# imu_v2.net
KiCad netlist of a schematic drawn in EAGLE
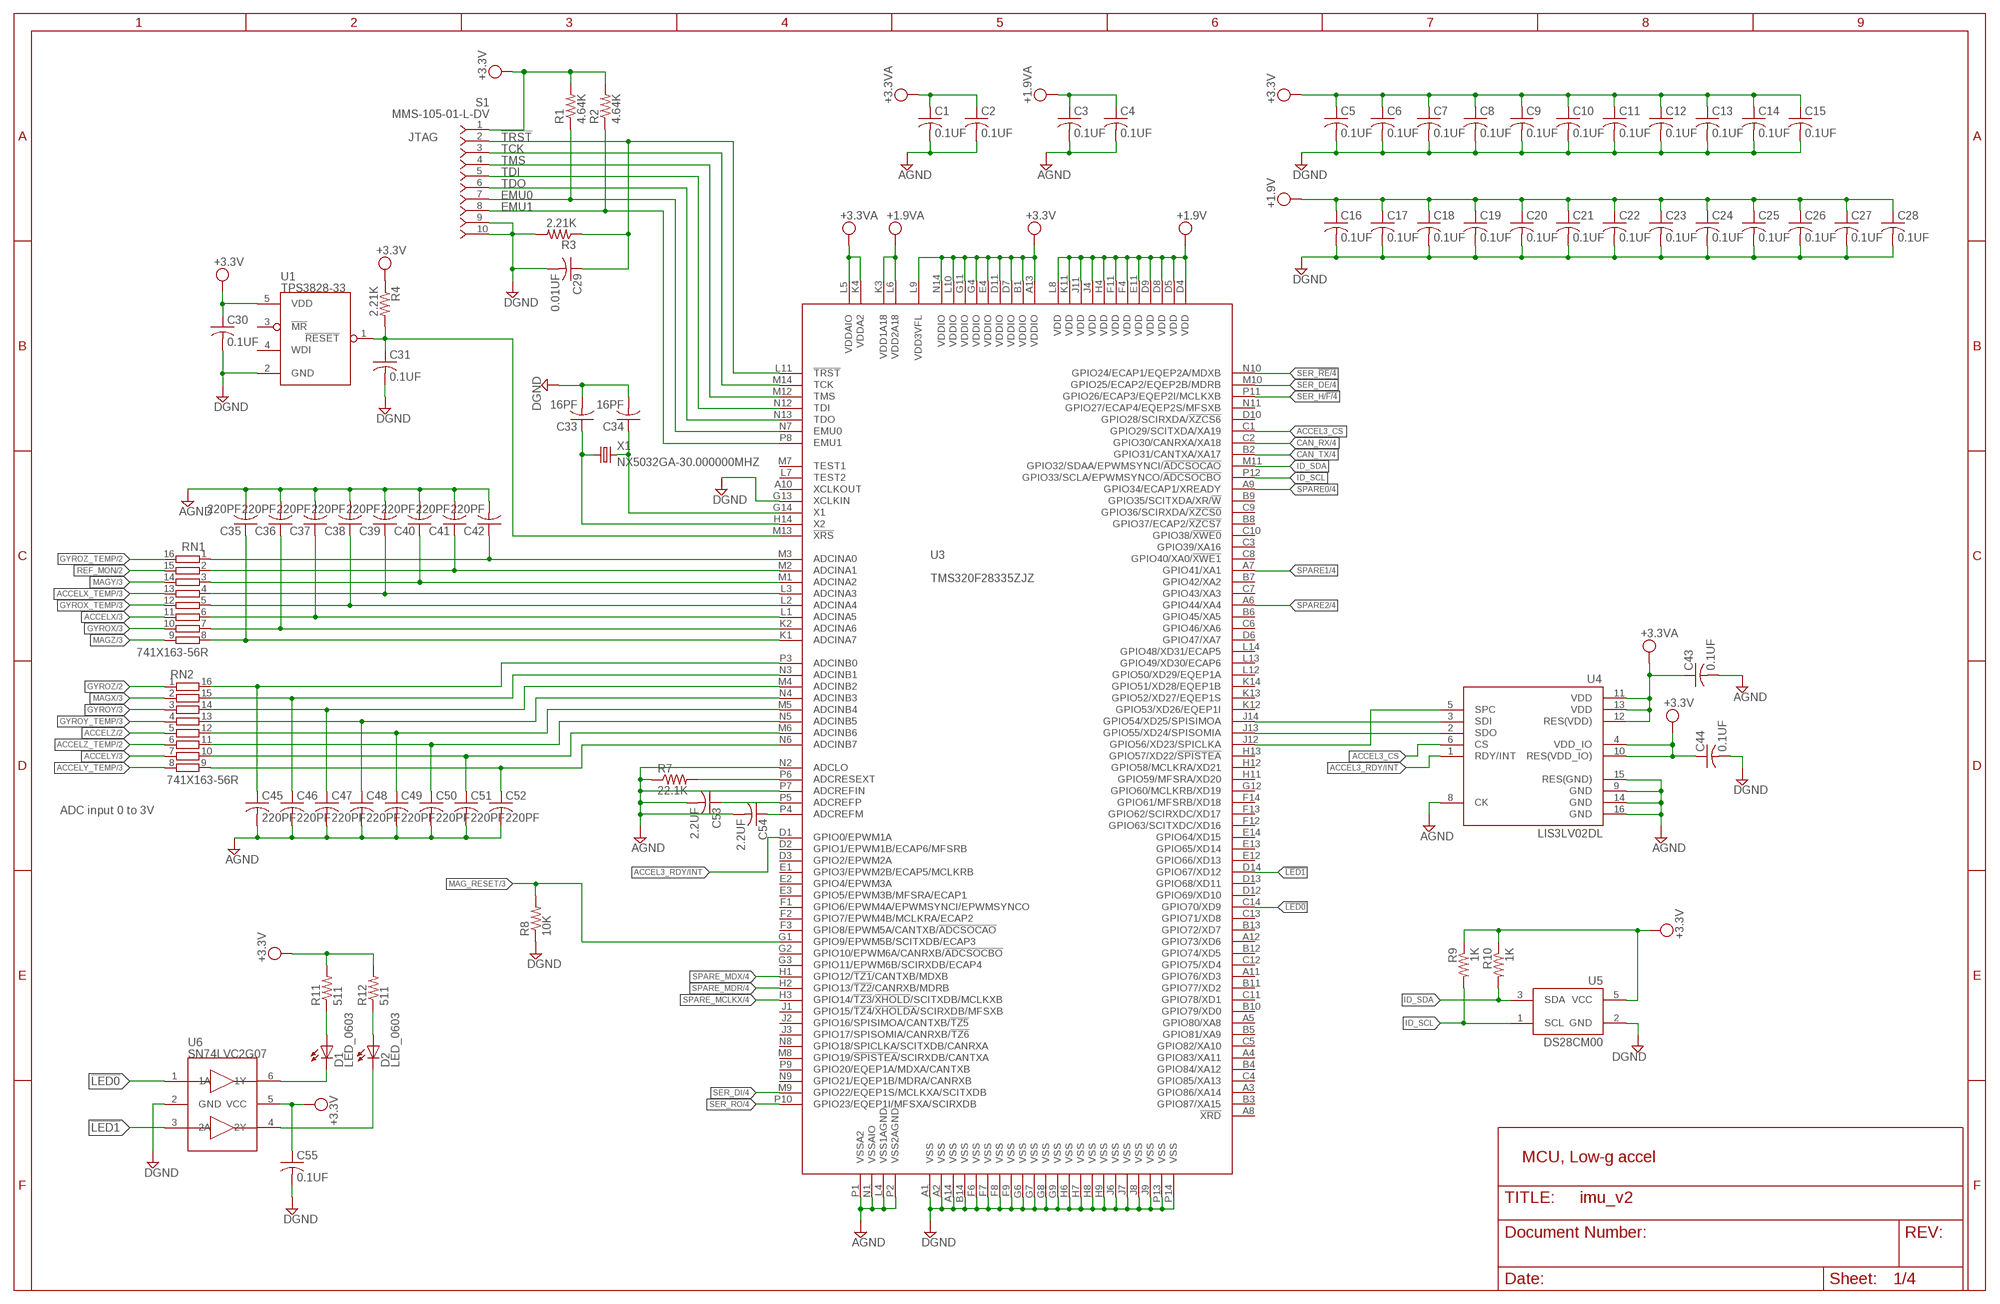
[diagram p0: schematic, sheet 1]
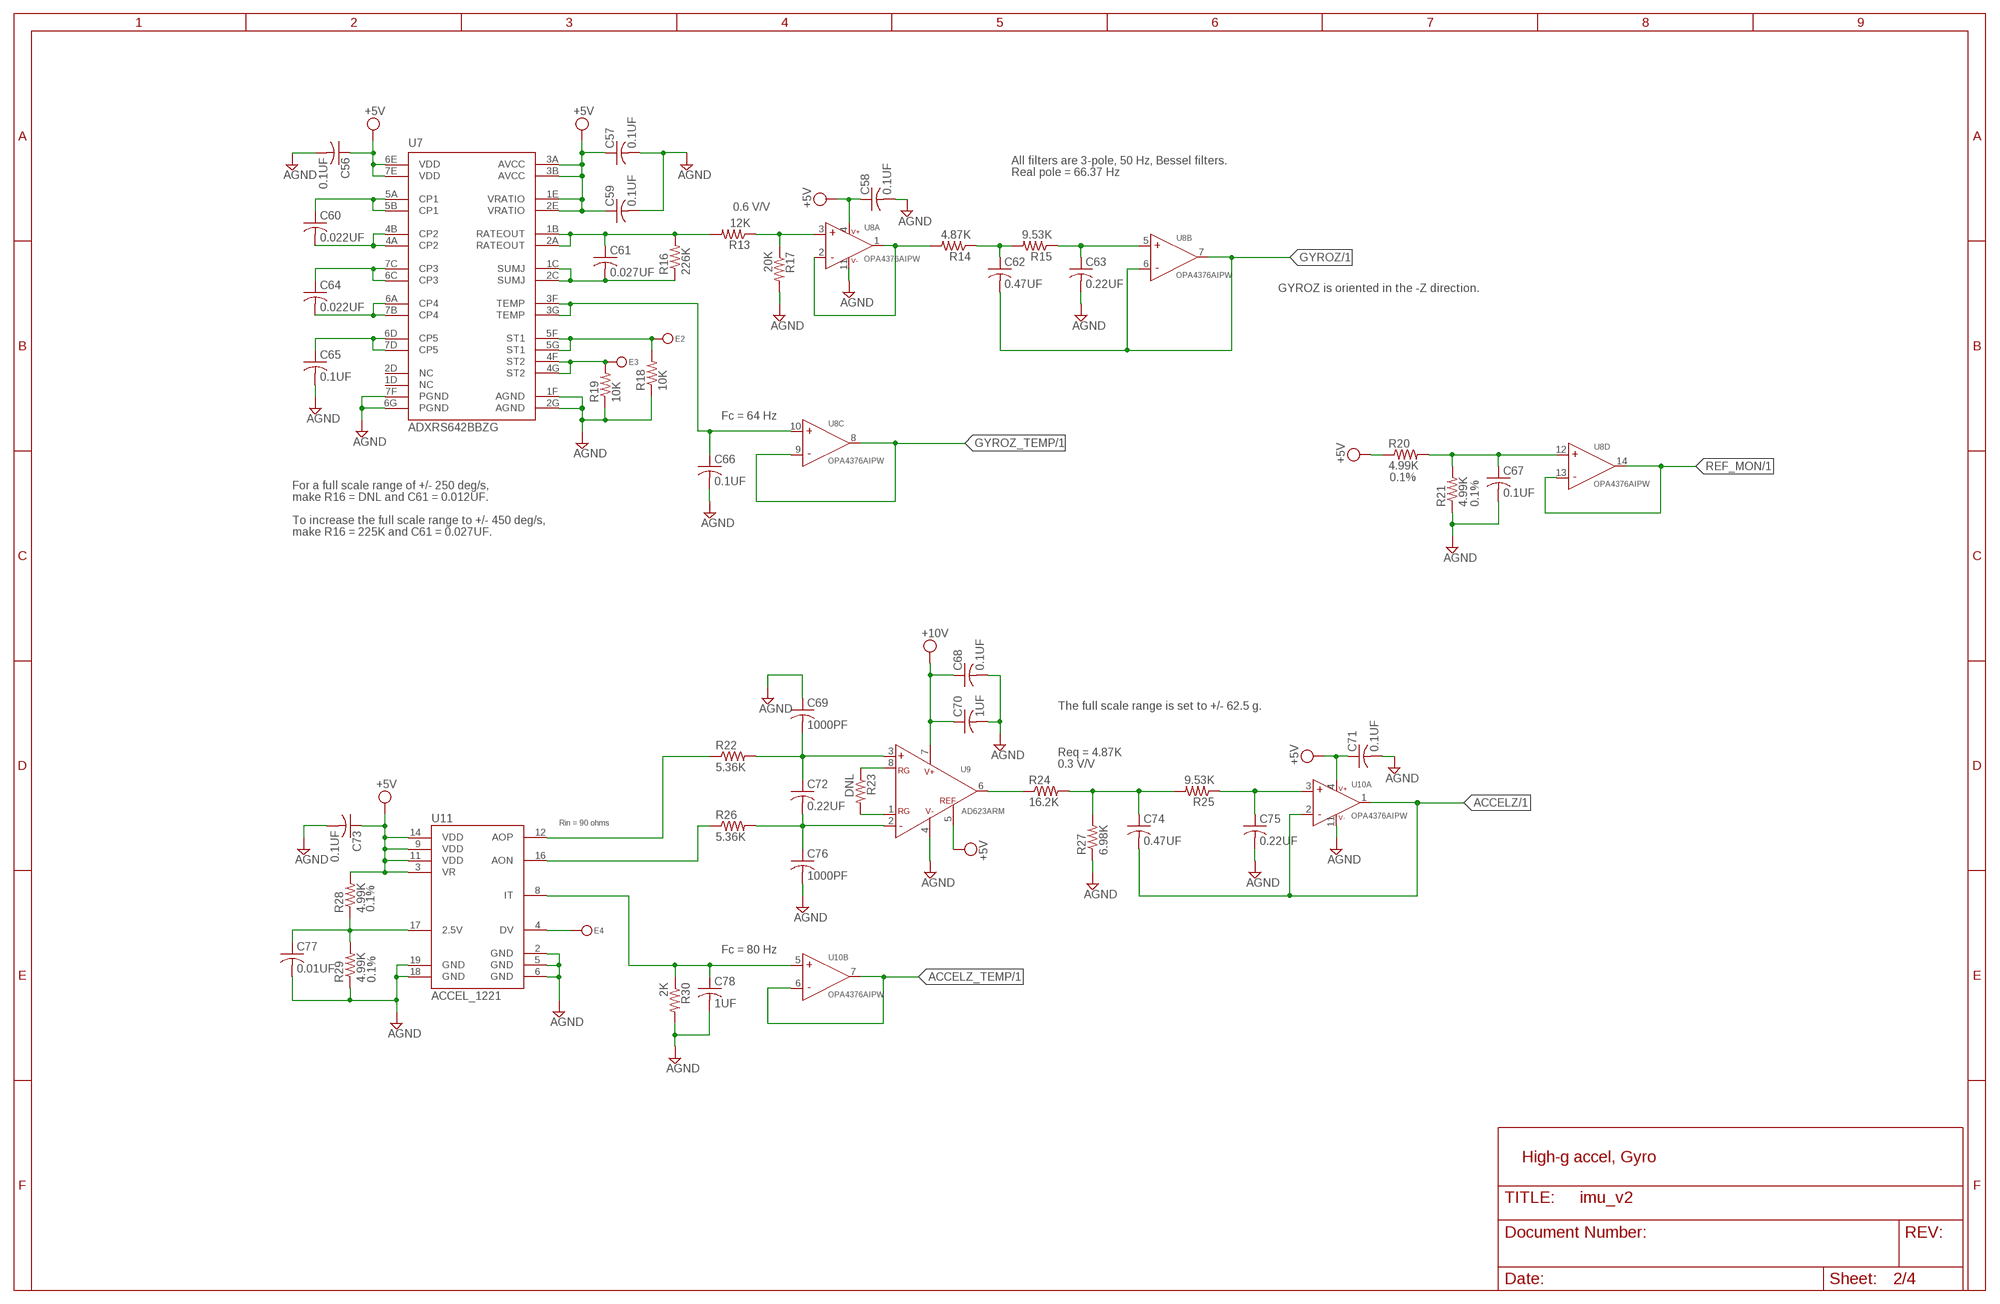
[diagram p1: schematic, sheet 2]
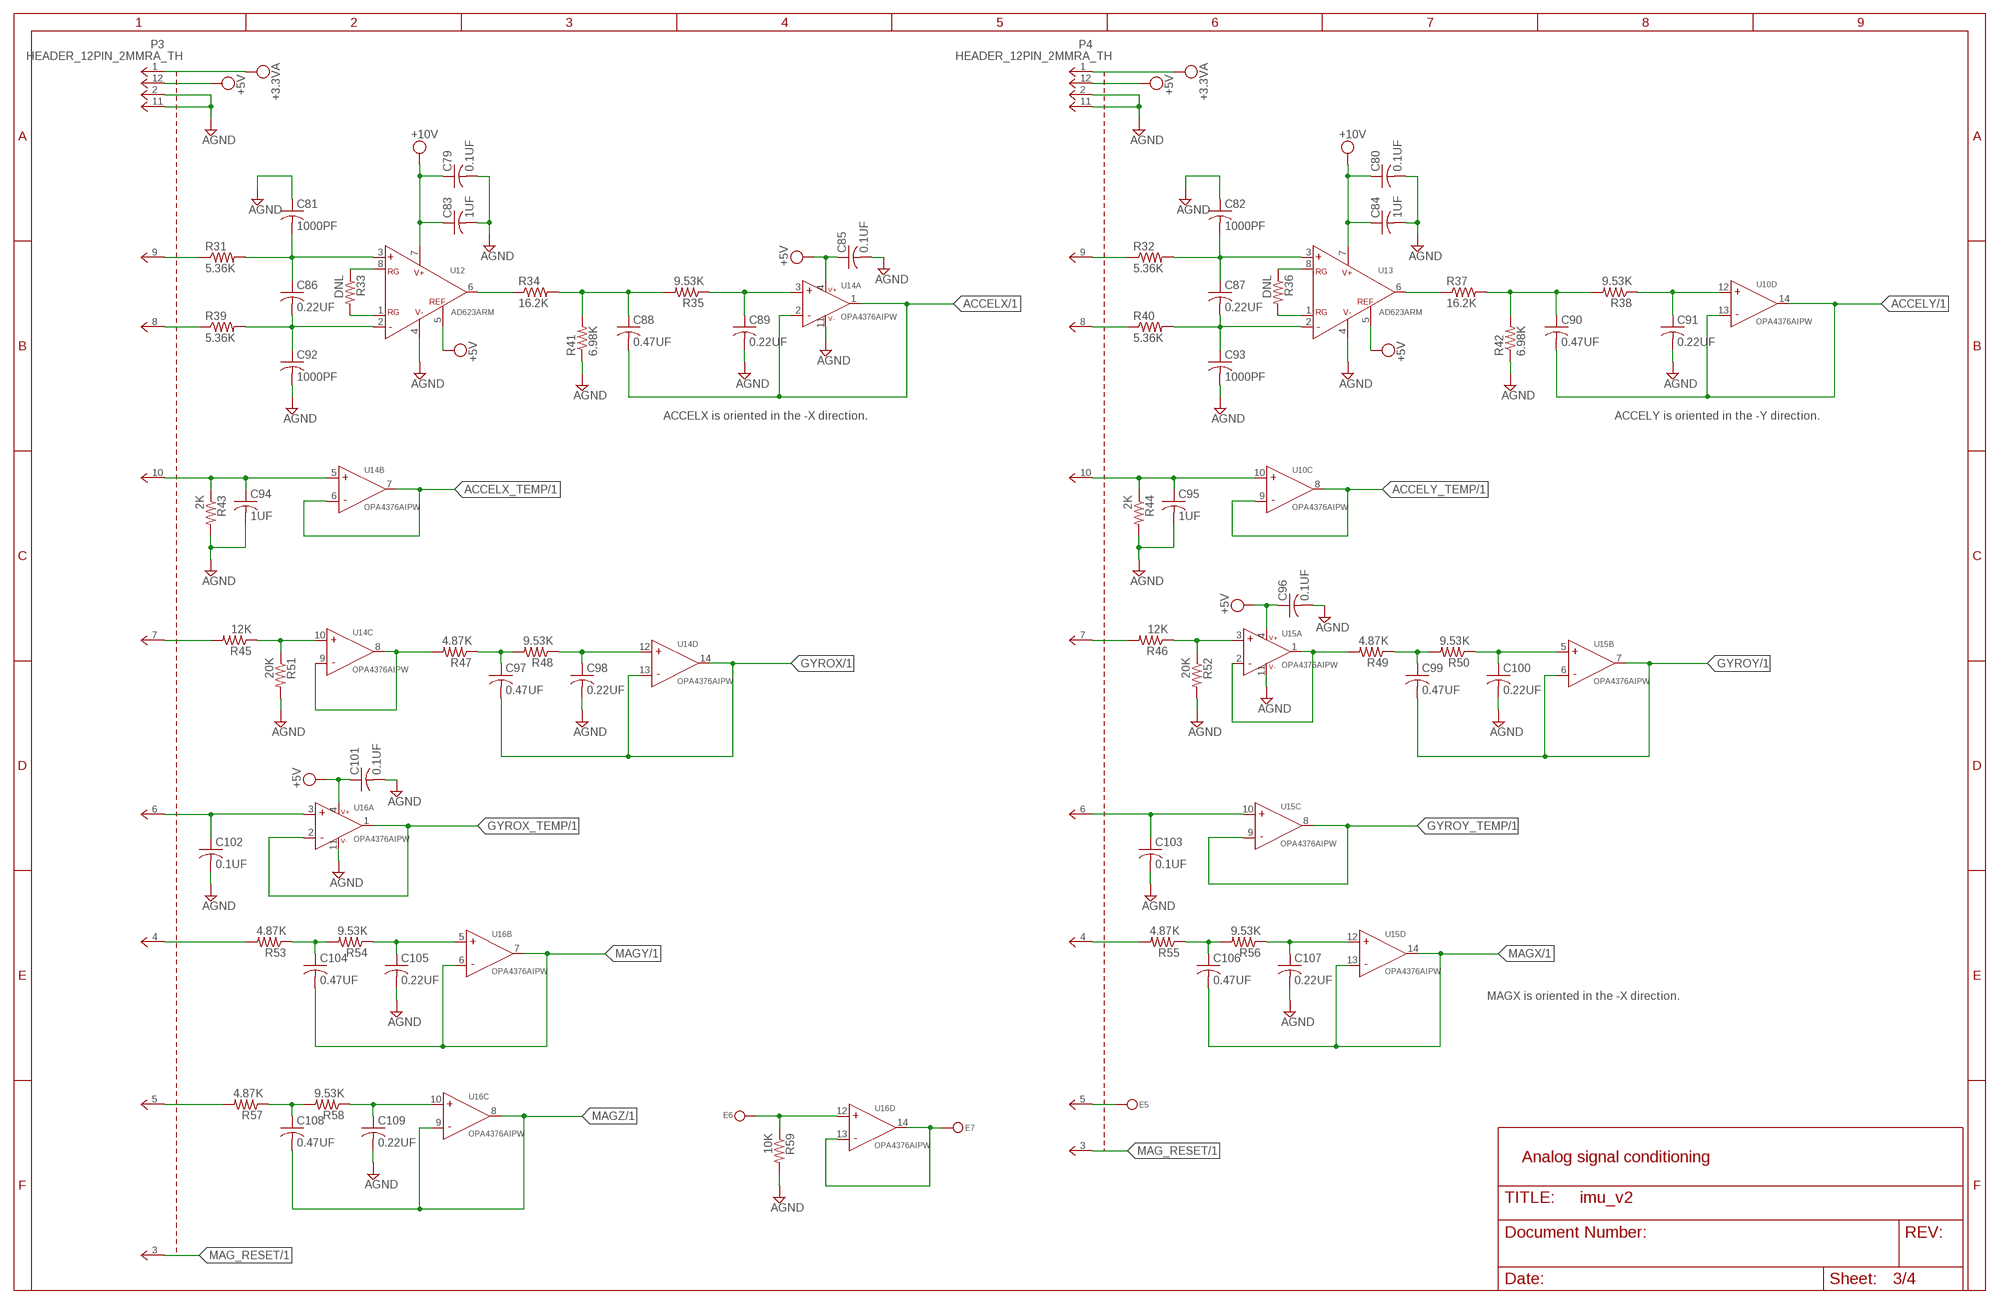
[diagram p2: schematic, sheet 3]
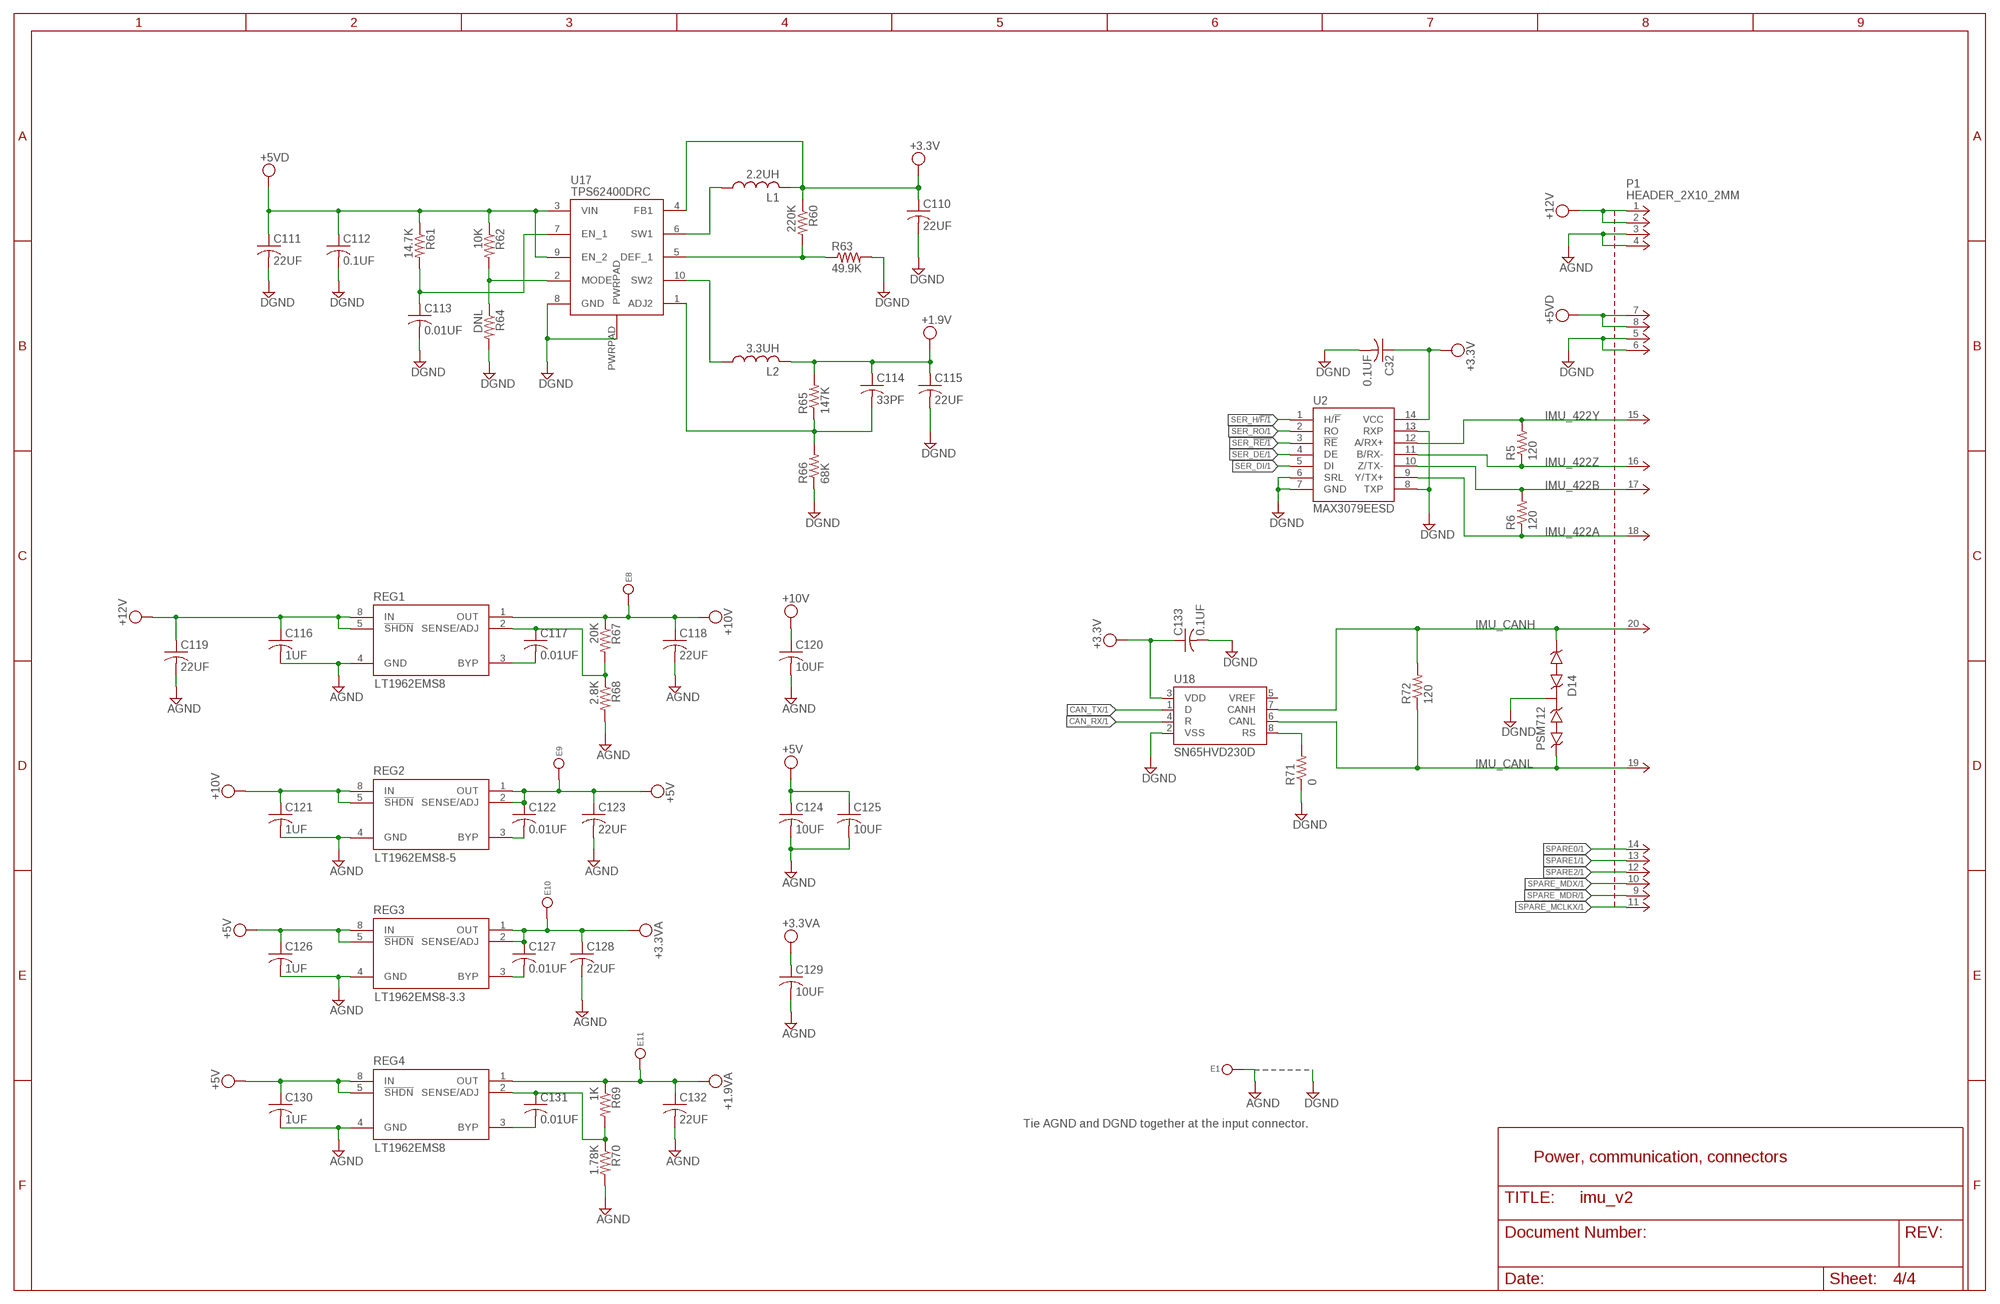
[diagram p3: schematic, sheet 4]

(export (version "E")
  (design (tool "Eeschema 10.0.6"))
  (components
    (comp (ref "C32")
      (value "0.1UF")
      (footprint "eagle-import:C0603K")
      (libsource (lib "eagle-import") (part "C-USC0603K"))
    )
    (comp (ref "C110")
      (value "22UF")
      (footprint "eagle-import:C1210K")
      (libsource (lib "eagle-import") (part "C-USC1210K"))
    )
    (comp (ref "C111")
      (value "22UF")
      (footprint "eagle-import:C1210K")
      (libsource (lib "eagle-import") (part "C-USC1210K"))
    )
    (comp (ref "C112")
      (value "0.1UF")
      (footprint "eagle-import:C0603K")
      (libsource (lib "eagle-import") (part "C-USC0603K"))
    )
    (comp (ref "C113")
      (value "0.01UF")
      (footprint "eagle-import:C0603K")
      (libsource (lib "eagle-import") (part "C-USC0603K"))
    )
    (comp (ref "C114")
      (value "33PF")
      (footprint "eagle-import:C0603K")
      (libsource (lib "eagle-import") (part "C-USC0603K"))
    )
    (comp (ref "C115")
      (value "22UF")
      (footprint "eagle-import:C1210K")
      (libsource (lib "eagle-import") (part "C-USC1210K"))
    )
    (comp (ref "C116")
      (value "1UF")
      (footprint "eagle-import:C0603K")
      (libsource (lib "eagle-import") (part "C-USC0603K"))
    )
    (comp (ref "C117")
      (value "0.01UF")
      (footprint "eagle-import:C0603K")
      (libsource (lib "eagle-import") (part "C-USC0603K"))
    )
    (comp (ref "C118")
      (value "22UF")
      (footprint "eagle-import:C1210K")
      (libsource (lib "eagle-import") (part "C-USC1210K"))
    )
    (comp (ref "C119")
      (value "22UF")
      (footprint "eagle-import:C1210K")
      (libsource (lib "eagle-import") (part "C-USC1210K"))
    )
    (comp (ref "C120")
      (value "10UF")
      (footprint "eagle-import:C1206K")
      (libsource (lib "eagle-import") (part "C-USC1206K"))
    )
    (comp (ref "C121")
      (value "1UF")
      (footprint "eagle-import:C0603K")
      (libsource (lib "eagle-import") (part "C-USC0603K"))
    )
    (comp (ref "C122")
      (value "0.01UF")
      (footprint "eagle-import:C0603K")
      (libsource (lib "eagle-import") (part "C-USC0603K"))
    )
    (comp (ref "C123")
      (value "22UF")
      (footprint "eagle-import:C1210K")
      (libsource (lib "eagle-import") (part "C-USC1210K"))
    )
    (comp (ref "C124")
      (value "10UF")
      (footprint "eagle-import:C1206K")
      (libsource (lib "eagle-import") (part "C-USC1206K"))
    )
    (comp (ref "C125")
      (value "10UF")
      (footprint "eagle-import:C1206K")
      (libsource (lib "eagle-import") (part "C-USC1206K"))
    )
    (comp (ref "C126")
      (value "1UF")
      (footprint "eagle-import:C0603K")
      (libsource (lib "eagle-import") (part "C-USC0603K"))
    )
    (comp (ref "C127")
      (value "0.01UF")
      (footprint "eagle-import:C0603K")
      (libsource (lib "eagle-import") (part "C-USC0603K"))
    )
    (comp (ref "C128")
      (value "22UF")
      (footprint "eagle-import:C1210K")
      (libsource (lib "eagle-import") (part "C-USC1210K"))
    )
    (comp (ref "C129")
      (value "10UF")
      (footprint "eagle-import:C1206K")
      (libsource (lib "eagle-import") (part "C-USC1206K"))
    )
    (comp (ref "C130")
      (value "1UF")
      (footprint "eagle-import:C0603K")
      (libsource (lib "eagle-import") (part "C-USC0603K"))
    )
    (comp (ref "C131")
      (value "0.01UF")
      (footprint "eagle-import:C0603K")
      (libsource (lib "eagle-import") (part "C-USC0603K"))
    )
    (comp (ref "C132")
      (value "22UF")
      (footprint "eagle-import:C1210K")
      (libsource (lib "eagle-import") (part "C-USC1210K"))
    )
    (comp (ref "C133")
      (value "0.1UF")
      (footprint "eagle-import:C0603K")
      (libsource (lib "eagle-import") (part "C-USC0603K"))
    )
    (comp (ref "D14")
      (value "PSM712")
      (footprint "eagle-import:SOT23")
      (libsource (lib "eagle-import") (part "PSM712"))
    )
    (comp (ref "E1")
      (value "5015_TESTCLIP")
      (footprint "eagle-import:5015_TESTCLIP")
      (libsource (lib "eagle-import") (part "5015_TESTCLIP"))
    )
    (comp (ref "E8")
      (value "TP30")
      (footprint "eagle-import:TP30")
      (libsource (lib "eagle-import") (part "TP30"))
    )
    (comp (ref "E9")
      (value "TP30")
      (footprint "eagle-import:TP30")
      (libsource (lib "eagle-import") (part "TP30"))
    )
    (comp (ref "E10")
      (value "TP30")
      (footprint "eagle-import:TP30")
      (libsource (lib "eagle-import") (part "TP30"))
    )
    (comp (ref "E11")
      (value "TP30")
      (footprint "eagle-import:TP30")
      (libsource (lib "eagle-import") (part "TP30"))
    )
    (comp (ref "L1")
      (value "2.2UH")
      (footprint "eagle-import:VLF3010A")
      (libsource (lib "eagle-import") (part "LVLF3010A2.2_UH"))
    )
    (comp (ref "L2")
      (value "3.3UH")
      (footprint "eagle-import:VLF3010A")
      (libsource (lib "eagle-import") (part "LVLF3010A3.3_UH"))
    )
    (comp (ref "P1")
      (value "HEADER_2X10_2MM")
      (footprint "eagle-import:HEADER_2X10_2MM")
      (libsource (lib "eagle-import") (part "HEADER_2X10_2MM"))
    )
    (comp (ref "R5")
      (value "120")
      (footprint "eagle-import:R0603")
      (libsource (lib "eagle-import") (part "R-US_R0603"))
    )
    (comp (ref "R6")
      (value "120")
      (footprint "eagle-import:R0603")
      (libsource (lib "eagle-import") (part "R-US_R0603"))
    )
    (comp (ref "R60")
      (value "220K")
      (footprint "eagle-import:R0603")
      (libsource (lib "eagle-import") (part "R-US_R0603"))
    )
    (comp (ref "R61")
      (value "14.7K")
      (footprint "eagle-import:R0603")
      (libsource (lib "eagle-import") (part "R-US_R0603"))
    )
    (comp (ref "R62")
      (value "10K")
      (footprint "eagle-import:R0603")
      (libsource (lib "eagle-import") (part "R-US_R0603"))
    )
    (comp (ref "R63")
      (value "49.9K")
      (footprint "eagle-import:R0603")
      (libsource (lib "eagle-import") (part "R-US_R0603"))
    )
    (comp (ref "R64")
      (value "DNL")
      (footprint "eagle-import:R0603")
      (libsource (lib "eagle-import") (part "R-US_R0603"))
    )
    (comp (ref "R65")
      (value "147K")
      (footprint "eagle-import:R0603")
      (libsource (lib "eagle-import") (part "R-US_R0603"))
    )
    (comp (ref "R66")
      (value "68K")
      (footprint "eagle-import:R0603")
      (libsource (lib "eagle-import") (part "R-US_R0603"))
    )
    (comp (ref "R67")
      (value "20K")
      (footprint "eagle-import:R0603")
      (libsource (lib "eagle-import") (part "R-US_R0603"))
    )
    (comp (ref "R68")
      (value "2.8K")
      (footprint "eagle-import:R0603")
      (libsource (lib "eagle-import") (part "R-US_R0603"))
    )
    (comp (ref "R69")
      (value "1K")
      (footprint "eagle-import:R0603")
      (libsource (lib "eagle-import") (part "R-US_R0603"))
    )
    (comp (ref "R70")
      (value "1.78K")
      (footprint "eagle-import:R0603")
      (libsource (lib "eagle-import") (part "R-US_R0603"))
    )
    (comp (ref "R71")
      (value "0")
      (footprint "eagle-import:R0603")
      (libsource (lib "eagle-import") (part "R-US_R0603"))
    )
    (comp (ref "R72")
      (value "120")
      (footprint "eagle-import:R0603")
      (libsource (lib "eagle-import") (part "R-US_R0603"))
    )
    (comp (ref "REG1")
      (value "LT1962EMS8")
      (footprint "eagle-import:MSOP8")
      (libsource (lib "eagle-import") (part "LT162EMS89"))
    )
    (comp (ref "REG2")
      (value "LT1962EMS8-5")
      (footprint "eagle-import:MSOP8")
      (libsource (lib "eagle-import") (part "LT162EMS8-59"))
    )
    (comp (ref "REG3")
      (value "LT1962EMS8-3.3")
      (footprint "eagle-import:MSOP8")
      (libsource (lib "eagle-import") (part "LT162EMS8-3.39"))
    )
    (comp (ref "REG4")
      (value "LT1962EMS8")
      (footprint "eagle-import:MSOP8")
      (libsource (lib "eagle-import") (part "LT162EMS89"))
    )
    (comp (ref "U2")
      (value "MAX3079EESD")
      (footprint "eagle-import:SOIC14-NARROW")
      (libsource (lib "eagle-import") (part "MAX3079EESD"))
    )
    (comp (ref "U17")
      (value "TPS62400DRC")
      (footprint "eagle-import:QFN10")
      (libsource (lib "eagle-import") (part "TPS624DRC00"))
    )
    (comp (ref "U18")
      (value "SN65HVD230D")
      (footprint "eagle-import:SO08")
      (libsource (lib "eagle-import") (part "SN65HVD230D"))
    )
    (comp (ref "C56")
      (value "0.1UF")
      (footprint "eagle-import:C0603K")
      (libsource (lib "eagle-import") (part "C-USC0603K"))
    )
    (comp (ref "C57")
      (value "0.1UF")
      (footprint "eagle-import:C0603K")
      (libsource (lib "eagle-import") (part "C-USC0603K"))
    )
    (comp (ref "C58")
      (value "0.1UF")
      (footprint "eagle-import:C0603K")
      (libsource (lib "eagle-import") (part "C-USC0603K"))
    )
    (comp (ref "C59")
      (value "0.1UF")
      (footprint "eagle-import:C0603K")
      (libsource (lib "eagle-import") (part "C-USC0603K"))
    )
    (comp (ref "C60")
      (value "0.022UF")
      (footprint "eagle-import:C0603K")
      (libsource (lib "eagle-import") (part "C-USC0603K"))
    )
    (comp (ref "C61")
      (value "0.027UF")
      (footprint "eagle-import:C0603K")
      (libsource (lib "eagle-import") (part "C-USC0603K"))
    )
    (comp (ref "C62")
      (value "0.47UF")
      (footprint "eagle-import:C0603K")
      (libsource (lib "eagle-import") (part "C-USC0603K"))
    )
    (comp (ref "C63")
      (value "0.22UF")
      (footprint "eagle-import:C0603K")
      (libsource (lib "eagle-import") (part "C-USC0603K"))
    )
    (comp (ref "C64")
      (value "0.022UF")
      (footprint "eagle-import:C0603K")
      (libsource (lib "eagle-import") (part "C-USC0603K"))
    )
    (comp (ref "C65")
      (value "0.1UF")
      (footprint "eagle-import:C0603K")
      (libsource (lib "eagle-import") (part "C-USC0603K"))
    )
    (comp (ref "C66")
      (value "0.1UF")
      (footprint "eagle-import:C0603K")
      (libsource (lib "eagle-import") (part "C-USC0603K"))
    )
    (comp (ref "C67")
      (value "0.1UF")
      (footprint "eagle-import:C0603K")
      (libsource (lib "eagle-import") (part "C-USC0603K"))
    )
    (comp (ref "C68")
      (value "0.1UF")
      (footprint "eagle-import:C0603K")
      (libsource (lib "eagle-import") (part "C-USC0603K"))
    )
    (comp (ref "C69")
      (value "1000PF")
      (footprint "eagle-import:C0603K")
      (libsource (lib "eagle-import") (part "C-USC0603K"))
    )
    (comp (ref "C70")
      (value "1UF")
      (footprint "eagle-import:C0603K")
      (libsource (lib "eagle-import") (part "C-USC0603K"))
    )
    (comp (ref "C71")
      (value "0.1UF")
      (footprint "eagle-import:C0603K")
      (libsource (lib "eagle-import") (part "C-USC0603K"))
    )
    (comp (ref "C72")
      (value "0.22UF")
      (footprint "eagle-import:C0603K")
      (libsource (lib "eagle-import") (part "C-USC0603K"))
    )
    (comp (ref "C73")
      (value "0.1UF")
      (footprint "eagle-import:C0603K")
      (libsource (lib "eagle-import") (part "C-USC0603K"))
    )
    (comp (ref "C74")
      (value "0.47UF")
      (footprint "eagle-import:C0603K")
      (libsource (lib "eagle-import") (part "C-USC0603K"))
    )
    (comp (ref "C75")
      (value "0.22UF")
      (footprint "eagle-import:C0603K")
      (libsource (lib "eagle-import") (part "C-USC0603K"))
    )
    (comp (ref "C76")
      (value "1000PF")
      (footprint "eagle-import:C0603K")
      (libsource (lib "eagle-import") (part "C-USC0603K"))
    )
    (comp (ref "C77")
      (value "0.01UF")
      (footprint "eagle-import:C0603K")
      (libsource (lib "eagle-import") (part "C-USC0603K"))
    )
    (comp (ref "C78")
      (value "1UF")
      (footprint "eagle-import:C0603K")
      (libsource (lib "eagle-import") (part "C-USC0603K"))
    )
    (comp (ref "E2")
      (value "TP30")
      (footprint "eagle-import:TP30")
      (libsource (lib "eagle-import") (part "TP30"))
    )
    (comp (ref "E3")
      (value "TP30")
      (footprint "eagle-import:TP30")
      (libsource (lib "eagle-import") (part "TP30"))
    )
    (comp (ref "E4")
      (value "TP30")
      (footprint "eagle-import:TP30")
      (libsource (lib "eagle-import") (part "TP30"))
    )
    (comp (ref "R13")
      (value "12K")
      (footprint "eagle-import:R0603")
      (libsource (lib "eagle-import") (part "R-US_R0603"))
    )
    (comp (ref "R14")
      (value "4.87K")
      (footprint "eagle-import:R0603")
      (libsource (lib "eagle-import") (part "R-US_R0603"))
    )
    (comp (ref "R15")
      (value "9.53K")
      (footprint "eagle-import:R0603")
      (libsource (lib "eagle-import") (part "R-US_R0603"))
    )
    (comp (ref "R16")
      (value "226K")
      (footprint "eagle-import:R0603")
      (libsource (lib "eagle-import") (part "R-US_R0603"))
    )
    (comp (ref "R17")
      (value "20K")
      (footprint "eagle-import:R0603")
      (libsource (lib "eagle-import") (part "R-US_R0603"))
    )
    (comp (ref "R18")
      (value "10K")
      (footprint "eagle-import:R0603")
      (libsource (lib "eagle-import") (part "R-US_R0603"))
    )
    (comp (ref "R19")
      (value "10K")
      (footprint "eagle-import:R0603")
      (libsource (lib "eagle-import") (part "R-US_R0603"))
    )
    (comp (ref "R20")
      (value "4.99K")
      (footprint "eagle-import:R0603")
      (fields (field (name "TOL") "0.1%"))
      (libsource (lib "eagle-import") (part "R-US_R0603"))
    )
    (comp (ref "R21")
      (value "4.99K")
      (footprint "eagle-import:R0603")
      (fields (field (name "TOL") "0.1%"))
      (libsource (lib "eagle-import") (part "R-US_R0603"))
    )
    (comp (ref "R22")
      (value "5.36K")
      (footprint "eagle-import:R0603")
      (libsource (lib "eagle-import") (part "R-US_R0603"))
    )
    (comp (ref "R23")
      (value "DNL")
      (footprint "eagle-import:R0603")
      (libsource (lib "eagle-import") (part "R-US_R0603"))
    )
    (comp (ref "R24")
      (value "16.2K")
      (footprint "eagle-import:R0603")
      (libsource (lib "eagle-import") (part "R-US_R0603"))
    )
    (comp (ref "R25")
      (value "9.53K")
      (footprint "eagle-import:R0603")
      (libsource (lib "eagle-import") (part "R-US_R0603"))
    )
    (comp (ref "R26")
      (value "5.36K")
      (footprint "eagle-import:R0603")
      (libsource (lib "eagle-import") (part "R-US_R0603"))
    )
    (comp (ref "R27")
      (value "6.98K")
      (footprint "eagle-import:R0603")
      (libsource (lib "eagle-import") (part "R-US_R0603"))
    )
    (comp (ref "R28")
      (value "4.99K")
      (footprint "eagle-import:R0603")
      (fields (field (name "TOL") "0.1%"))
      (libsource (lib "eagle-import") (part "R-US_R0603"))
    )
    (comp (ref "R29")
      (value "4.99K")
      (footprint "eagle-import:R0603")
      (fields (field (name "TOL") "0.1%"))
      (libsource (lib "eagle-import") (part "R-US_R0603"))
    )
    (comp (ref "R30")
      (value "2K")
      (footprint "eagle-import:R0603")
      (libsource (lib "eagle-import") (part "R-US_R0603"))
    )
    (comp (ref "U7")
      (value "ADXRS642BBZG")
      (footprint "eagle-import:ADXRS_CBGA32")
      (libsource (lib "eagle-import") (part "ADXRSBBZG642"))
    )
    (comp (ref "U8")
      (value "OPA4376AIPW")
      (footprint "eagle-import:TSSOP14")
      (libsource (lib "eagle-import") (part "OPA4376AIPW"))
    )
    (comp (ref "U9")
      (value "AD623ARM")
      (footprint "eagle-import:MSOP8")
      (libsource (lib "eagle-import") (part "AD623ARM"))
    )
    (comp (ref "U10")
      (value "OPA4376AIPW")
      (footprint "eagle-import:TSSOP14")
      (libsource (lib "eagle-import") (part "OPA4376AIPW"))
    )
    (comp (ref "U11")
      (value "ACCEL_1221")
      (footprint "eagle-import:1221_LCC")
      (libsource (lib "eagle-import") (part "ACCEL_1221"))
    )
    (comp (ref "C79")
      (value "0.1UF")
      (footprint "eagle-import:C0603K")
      (libsource (lib "eagle-import") (part "C-USC0603K"))
    )
    (comp (ref "C80")
      (value "0.1UF")
      (footprint "eagle-import:C0603K")
      (libsource (lib "eagle-import") (part "C-USC0603K"))
    )
    (comp (ref "C81")
      (value "1000PF")
      (footprint "eagle-import:C0603K")
      (libsource (lib "eagle-import") (part "C-USC0603K"))
    )
    (comp (ref "C82")
      (value "1000PF")
      (footprint "eagle-import:C0603K")
      (libsource (lib "eagle-import") (part "C-USC0603K"))
    )
    (comp (ref "C83")
      (value "1UF")
      (footprint "eagle-import:C0603K")
      (libsource (lib "eagle-import") (part "C-USC0603K"))
    )
    (comp (ref "C84")
      (value "1UF")
      (footprint "eagle-import:C0603K")
      (libsource (lib "eagle-import") (part "C-USC0603K"))
    )
    (comp (ref "C85")
      (value "0.1UF")
      (footprint "eagle-import:C0603K")
      (libsource (lib "eagle-import") (part "C-USC0603K"))
    )
    (comp (ref "C86")
      (value "0.22UF")
      (footprint "eagle-import:C0603K")
      (libsource (lib "eagle-import") (part "C-USC0603K"))
    )
    (comp (ref "C87")
      (value "0.22UF")
      (footprint "eagle-import:C0603K")
      (libsource (lib "eagle-import") (part "C-USC0603K"))
    )
    (comp (ref "C88")
      (value "0.47UF")
      (footprint "eagle-import:C0603K")
      (libsource (lib "eagle-import") (part "C-USC0603K"))
    )
    (comp (ref "C89")
      (value "0.22UF")
      (footprint "eagle-import:C0603K")
      (libsource (lib "eagle-import") (part "C-USC0603K"))
    )
    (comp (ref "C90")
      (value "0.47UF")
      (footprint "eagle-import:C0603K")
      (libsource (lib "eagle-import") (part "C-USC0603K"))
    )
    (comp (ref "C91")
      (value "0.22UF")
      (footprint "eagle-import:C0603K")
      (libsource (lib "eagle-import") (part "C-USC0603K"))
    )
    (comp (ref "C92")
      (value "1000PF")
      (footprint "eagle-import:C0603K")
      (libsource (lib "eagle-import") (part "C-USC0603K"))
    )
    (comp (ref "C93")
      (value "1000PF")
      (footprint "eagle-import:C0603K")
      (libsource (lib "eagle-import") (part "C-USC0603K"))
    )
    (comp (ref "C94")
      (value "1UF")
      (footprint "eagle-import:C0603K")
      (libsource (lib "eagle-import") (part "C-USC0603K"))
    )
    (comp (ref "C95")
      (value "1UF")
      (footprint "eagle-import:C0603K")
      (libsource (lib "eagle-import") (part "C-USC0603K"))
    )
    (comp (ref "C96")
      (value "0.1UF")
      (footprint "eagle-import:C0603K")
      (libsource (lib "eagle-import") (part "C-USC0603K"))
    )
    (comp (ref "C97")
      (value "0.47UF")
      (footprint "eagle-import:C0603K")
      (libsource (lib "eagle-import") (part "C-USC0603K"))
    )
    (comp (ref "C98")
      (value "0.22UF")
      (footprint "eagle-import:C0603K")
      (libsource (lib "eagle-import") (part "C-USC0603K"))
    )
    (comp (ref "C99")
      (value "0.47UF")
      (footprint "eagle-import:C0603K")
      (libsource (lib "eagle-import") (part "C-USC0603K"))
    )
    (comp (ref "C100")
      (value "0.22UF")
      (footprint "eagle-import:C0603K")
      (libsource (lib "eagle-import") (part "C-USC0603K"))
    )
    (comp (ref "C101")
      (value "0.1UF")
      (footprint "eagle-import:C0603K")
      (libsource (lib "eagle-import") (part "C-USC0603K"))
    )
    (comp (ref "C102")
      (value "0.1UF")
      (footprint "eagle-import:C0603K")
      (libsource (lib "eagle-import") (part "C-USC0603K"))
    )
    (comp (ref "C103")
      (value "0.1UF")
      (footprint "eagle-import:C0603K")
      (libsource (lib "eagle-import") (part "C-USC0603K"))
    )
    (comp (ref "C104")
      (value "0.47UF")
      (footprint "eagle-import:C0603K")
      (libsource (lib "eagle-import") (part "C-USC0603K"))
    )
    (comp (ref "C105")
      (value "0.22UF")
      (footprint "eagle-import:C0603K")
      (libsource (lib "eagle-import") (part "C-USC0603K"))
    )
    (comp (ref "C106")
      (value "0.47UF")
      (footprint "eagle-import:C0603K")
      (libsource (lib "eagle-import") (part "C-USC0603K"))
    )
    (comp (ref "C107")
      (value "0.22UF")
      (footprint "eagle-import:C0603K")
      (libsource (lib "eagle-import") (part "C-USC0603K"))
    )
    (comp (ref "C108")
      (value "0.47UF")
      (footprint "eagle-import:C0603K")
      (libsource (lib "eagle-import") (part "C-USC0603K"))
    )
    (comp (ref "C109")
      (value "0.22UF")
      (footprint "eagle-import:C0603K")
      (libsource (lib "eagle-import") (part "C-USC0603K"))
    )
    (comp (ref "E5")
      (value "TP30")
      (footprint "eagle-import:TP30")
      (libsource (lib "eagle-import") (part "TP30"))
    )
    (comp (ref "E6")
      (value "TP30")
      (footprint "eagle-import:TP30")
      (libsource (lib "eagle-import") (part "TP30"))
    )
    (comp (ref "E7")
      (value "TP30")
      (footprint "eagle-import:TP30")
      (libsource (lib "eagle-import") (part "TP30"))
    )
    (comp (ref "P3")
      (value "HEADER_12PIN_2MMRA_TH")
      (footprint "eagle-import:TMM-112-01-T-S-RA")
      (libsource (lib "eagle-import") (part "HEADER_12PIN_2MMRA_TH"))
    )
    (comp (ref "P4")
      (value "HEADER_12PIN_2MMRA_TH")
      (footprint "eagle-import:TMM-112-01-T-S-RA")
      (libsource (lib "eagle-import") (part "HEADER_12PIN_2MMRA_TH"))
    )
    (comp (ref "R31")
      (value "5.36K")
      (footprint "eagle-import:R0603")
      (libsource (lib "eagle-import") (part "R-US_R0603"))
    )
    (comp (ref "R32")
      (value "5.36K")
      (footprint "eagle-import:R0603")
      (libsource (lib "eagle-import") (part "R-US_R0603"))
    )
    (comp (ref "R33")
      (value "DNL")
      (footprint "eagle-import:R0603")
      (libsource (lib "eagle-import") (part "R-US_R0603"))
    )
    (comp (ref "R34")
      (value "16.2K")
      (footprint "eagle-import:R0603")
      (libsource (lib "eagle-import") (part "R-US_R0603"))
    )
    (comp (ref "R35")
      (value "9.53K")
      (footprint "eagle-import:R0603")
      (libsource (lib "eagle-import") (part "R-US_R0603"))
    )
    (comp (ref "R36")
      (value "DNL")
      (footprint "eagle-import:R0603")
      (libsource (lib "eagle-import") (part "R-US_R0603"))
    )
    (comp (ref "R37")
      (value "16.2K")
      (footprint "eagle-import:R0603")
      (libsource (lib "eagle-import") (part "R-US_R0603"))
    )
    (comp (ref "R38")
      (value "9.53K")
      (footprint "eagle-import:R0603")
      (libsource (lib "eagle-import") (part "R-US_R0603"))
    )
    (comp (ref "R39")
      (value "5.36K")
      (footprint "eagle-import:R0603")
      (libsource (lib "eagle-import") (part "R-US_R0603"))
    )
    (comp (ref "R40")
      (value "5.36K")
      (footprint "eagle-import:R0603")
      (libsource (lib "eagle-import") (part "R-US_R0603"))
    )
    (comp (ref "R41")
      (value "6.98K")
      (footprint "eagle-import:R0603")
      (libsource (lib "eagle-import") (part "R-US_R0603"))
    )
    (comp (ref "R42")
      (value "6.98K")
      (footprint "eagle-import:R0603")
      (libsource (lib "eagle-import") (part "R-US_R0603"))
    )
    (comp (ref "R43")
      (value "2K")
      (footprint "eagle-import:R0603")
      (libsource (lib "eagle-import") (part "R-US_R0603"))
    )
    (comp (ref "R44")
      (value "2K")
      (footprint "eagle-import:R0603")
      (libsource (lib "eagle-import") (part "R-US_R0603"))
    )
    (comp (ref "R45")
      (value "12K")
      (footprint "eagle-import:R0603")
      (libsource (lib "eagle-import") (part "R-US_R0603"))
    )
    (comp (ref "R46")
      (value "12K")
      (footprint "eagle-import:R0603")
      (libsource (lib "eagle-import") (part "R-US_R0603"))
    )
    (comp (ref "R47")
      (value "4.87K")
      (footprint "eagle-import:R0603")
      (libsource (lib "eagle-import") (part "R-US_R0603"))
    )
    (comp (ref "R48")
      (value "9.53K")
      (footprint "eagle-import:R0603")
      (libsource (lib "eagle-import") (part "R-US_R0603"))
    )
    (comp (ref "R49")
      (value "4.87K")
      (footprint "eagle-import:R0603")
      (libsource (lib "eagle-import") (part "R-US_R0603"))
    )
    (comp (ref "R50")
      (value "9.53K")
      (footprint "eagle-import:R0603")
      (libsource (lib "eagle-import") (part "R-US_R0603"))
    )
    (comp (ref "R51")
      (value "20K")
      (footprint "eagle-import:R0603")
      (libsource (lib "eagle-import") (part "R-US_R0603"))
    )
    (comp (ref "R52")
      (value "20K")
      (footprint "eagle-import:R0603")
      (libsource (lib "eagle-import") (part "R-US_R0603"))
    )
    (comp (ref "R53")
      (value "4.87K")
      (footprint "eagle-import:R0603")
      (libsource (lib "eagle-import") (part "R-US_R0603"))
    )
    (comp (ref "R54")
      (value "9.53K")
      (footprint "eagle-import:R0603")
      (libsource (lib "eagle-import") (part "R-US_R0603"))
    )
    (comp (ref "R55")
      (value "4.87K")
      (footprint "eagle-import:R0603")
      (libsource (lib "eagle-import") (part "R-US_R0603"))
    )
    (comp (ref "R56")
      (value "9.53K")
      (footprint "eagle-import:R0603")
      (libsource (lib "eagle-import") (part "R-US_R0603"))
    )
    (comp (ref "R57")
      (value "4.87K")
      (footprint "eagle-import:R0603")
      (libsource (lib "eagle-import") (part "R-US_R0603"))
    )
    (comp (ref "R58")
      (value "9.53K")
      (footprint "eagle-import:R0603")
      (libsource (lib "eagle-import") (part "R-US_R0603"))
    )
    (comp (ref "R59")
      (value "10K")
      (footprint "eagle-import:R0603")
      (libsource (lib "eagle-import") (part "R-US_R0603"))
    )
    (comp (ref "U12")
      (value "AD623ARM")
      (footprint "eagle-import:MSOP8")
      (libsource (lib "eagle-import") (part "AD623ARM"))
    )
    (comp (ref "U13")
      (value "AD623ARM")
      (footprint "eagle-import:MSOP8")
      (libsource (lib "eagle-import") (part "AD623ARM"))
    )
    (comp (ref "U14")
      (value "OPA4376AIPW")
      (footprint "eagle-import:TSSOP14")
      (libsource (lib "eagle-import") (part "OPA4376AIPW"))
    )
    (comp (ref "U15")
      (value "OPA4376AIPW")
      (footprint "eagle-import:TSSOP14")
      (libsource (lib "eagle-import") (part "OPA4376AIPW"))
    )
    (comp (ref "U16")
      (value "OPA4376AIPW")
      (footprint "eagle-import:TSSOP14")
      (libsource (lib "eagle-import") (part "OPA4376AIPW"))
    )
    (comp (ref "C1")
      (value "0.1UF")
      (footprint "eagle-import:C0603K")
      (libsource (lib "eagle-import") (part "C-USC0603K"))
    )
    (comp (ref "C2")
      (value "0.1UF")
      (footprint "eagle-import:C0603K")
      (libsource (lib "eagle-import") (part "C-USC0603K"))
    )
    (comp (ref "C3")
      (value "0.1UF")
      (footprint "eagle-import:C0603K")
      (libsource (lib "eagle-import") (part "C-USC0603K"))
    )
    (comp (ref "C4")
      (value "0.1UF")
      (footprint "eagle-import:C0603K")
      (libsource (lib "eagle-import") (part "C-USC0603K"))
    )
    (comp (ref "C5")
      (value "0.1UF")
      (footprint "eagle-import:C0603K")
      (libsource (lib "eagle-import") (part "C-USC0603K"))
    )
    (comp (ref "C6")
      (value "0.1UF")
      (footprint "eagle-import:C0603K")
      (libsource (lib "eagle-import") (part "C-USC0603K"))
    )
    (comp (ref "C7")
      (value "0.1UF")
      (footprint "eagle-import:C0603K")
      (libsource (lib "eagle-import") (part "C-USC0603K"))
    )
    (comp (ref "C8")
      (value "0.1UF")
      (footprint "eagle-import:C0603K")
      (libsource (lib "eagle-import") (part "C-USC0603K"))
    )
    (comp (ref "C9")
      (value "0.1UF")
      (footprint "eagle-import:C0603K")
      (libsource (lib "eagle-import") (part "C-USC0603K"))
    )
    (comp (ref "C10")
      (value "0.1UF")
      (footprint "eagle-import:C0603K")
      (libsource (lib "eagle-import") (part "C-USC0603K"))
    )
    (comp (ref "C11")
      (value "0.1UF")
      (footprint "eagle-import:C0603K")
      (libsource (lib "eagle-import") (part "C-USC0603K"))
    )
    (comp (ref "C12")
      (value "0.1UF")
      (footprint "eagle-import:C0603K")
      (libsource (lib "eagle-import") (part "C-USC0603K"))
    )
    (comp (ref "C13")
      (value "0.1UF")
      (footprint "eagle-import:C0603K")
      (libsource (lib "eagle-import") (part "C-USC0603K"))
    )
    (comp (ref "C14")
      (value "0.1UF")
      (footprint "eagle-import:C0603K")
      (libsource (lib "eagle-import") (part "C-USC0603K"))
    )
    (comp (ref "C15")
      (value "0.1UF")
      (footprint "eagle-import:C0603K")
      (libsource (lib "eagle-import") (part "C-USC0603K"))
    )
    (comp (ref "C16")
      (value "0.1UF")
      (footprint "eagle-import:C0603K")
      (libsource (lib "eagle-import") (part "C-USC0603K"))
    )
    (comp (ref "C17")
      (value "0.1UF")
      (footprint "eagle-import:C0603K")
      (libsource (lib "eagle-import") (part "C-USC0603K"))
    )
    (comp (ref "C18")
      (value "0.1UF")
      (footprint "eagle-import:C0603K")
      (libsource (lib "eagle-import") (part "C-USC0603K"))
    )
    (comp (ref "C19")
      (value "0.1UF")
      (footprint "eagle-import:C0603K")
      (libsource (lib "eagle-import") (part "C-USC0603K"))
    )
    (comp (ref "C20")
      (value "0.1UF")
      (footprint "eagle-import:C0603K")
      (libsource (lib "eagle-import") (part "C-USC0603K"))
    )
    (comp (ref "C21")
      (value "0.1UF")
      (footprint "eagle-import:C0603K")
      (libsource (lib "eagle-import") (part "C-USC0603K"))
    )
    (comp (ref "C22")
      (value "0.1UF")
      (footprint "eagle-import:C0603K")
      (libsource (lib "eagle-import") (part "C-USC0603K"))
    )
    (comp (ref "C23")
      (value "0.1UF")
      (footprint "eagle-import:C0603K")
      (libsource (lib "eagle-import") (part "C-USC0603K"))
    )
    (comp (ref "C24")
      (value "0.1UF")
      (footprint "eagle-import:C0603K")
      (libsource (lib "eagle-import") (part "C-USC0603K"))
    )
    (comp (ref "C25")
      (value "0.1UF")
      (footprint "eagle-import:C0603K")
      (libsource (lib "eagle-import") (part "C-USC0603K"))
    )
    (comp (ref "C26")
      (value "0.1UF")
      (footprint "eagle-import:C0603K")
      (libsource (lib "eagle-import") (part "C-USC0603K"))
    )
    (comp (ref "C27")
      (value "0.1UF")
      (footprint "eagle-import:C0603K")
      (libsource (lib "eagle-import") (part "C-USC0603K"))
    )
    (comp (ref "C28")
      (value "0.1UF")
      (footprint "eagle-import:C0603K")
      (libsource (lib "eagle-import") (part "C-USC0603K"))
    )
    (comp (ref "C29")
      (value "0.01UF")
      (footprint "eagle-import:C0603K")
      (libsource (lib "eagle-import") (part "C-USC0603K"))
    )
    (comp (ref "C30")
      (value "0.1UF")
      (footprint "eagle-import:C0603K")
      (libsource (lib "eagle-import") (part "C-USC0603K"))
    )
    (comp (ref "C31")
      (value "0.1UF")
      (footprint "eagle-import:C0603K")
      (libsource (lib "eagle-import") (part "C-USC0603K"))
    )
    (comp (ref "C33")
      (value "16PF")
      (footprint "eagle-import:C0603K")
      (libsource (lib "eagle-import") (part "C-USC0603K"))
    )
    (comp (ref "C34")
      (value "16PF")
      (footprint "eagle-import:C0603K")
      (libsource (lib "eagle-import") (part "C-USC0603K"))
    )
    (comp (ref "C35")
      (value "220PF")
      (footprint "eagle-import:C0603K")
      (libsource (lib "eagle-import") (part "C-USC0603K"))
    )
    (comp (ref "C36")
      (value "220PF")
      (footprint "eagle-import:C0603K")
      (libsource (lib "eagle-import") (part "C-USC0603K"))
    )
    (comp (ref "C37")
      (value "220PF")
      (footprint "eagle-import:C0603K")
      (libsource (lib "eagle-import") (part "C-USC0603K"))
    )
    (comp (ref "C38")
      (value "220PF")
      (footprint "eagle-import:C0603K")
      (libsource (lib "eagle-import") (part "C-USC0603K"))
    )
    (comp (ref "C39")
      (value "220PF")
      (footprint "eagle-import:C0603K")
      (libsource (lib "eagle-import") (part "C-USC0603K"))
    )
    (comp (ref "C40")
      (value "220PF")
      (footprint "eagle-import:C0603K")
      (libsource (lib "eagle-import") (part "C-USC0603K"))
    )
    (comp (ref "C41")
      (value "220PF")
      (footprint "eagle-import:C0603K")
      (libsource (lib "eagle-import") (part "C-USC0603K"))
    )
    (comp (ref "C42")
      (value "220PF")
      (footprint "eagle-import:C0603K")
      (libsource (lib "eagle-import") (part "C-USC0603K"))
    )
    (comp (ref "C43")
      (value "0.1UF")
      (footprint "eagle-import:C0603K")
      (libsource (lib "eagle-import") (part "C-USC0603K"))
    )
    (comp (ref "C44")
      (value "0.1UF")
      (footprint "eagle-import:C0603K")
      (libsource (lib "eagle-import") (part "C-USC0603K"))
    )
    (comp (ref "C45")
      (value "220PF")
      (footprint "eagle-import:C0603K")
      (libsource (lib "eagle-import") (part "C-USC0603K"))
    )
    (comp (ref "C46")
      (value "220PF")
      (footprint "eagle-import:C0603K")
      (libsource (lib "eagle-import") (part "C-USC0603K"))
    )
    (comp (ref "C47")
      (value "220PF")
      (footprint "eagle-import:C0603K")
      (libsource (lib "eagle-import") (part "C-USC0603K"))
    )
    (comp (ref "C48")
      (value "220PF")
      (footprint "eagle-import:C0603K")
      (libsource (lib "eagle-import") (part "C-USC0603K"))
    )
    (comp (ref "C49")
      (value "220PF")
      (footprint "eagle-import:C0603K")
      (libsource (lib "eagle-import") (part "C-USC0603K"))
    )
    (comp (ref "C50")
      (value "220PF")
      (footprint "eagle-import:C0603K")
      (libsource (lib "eagle-import") (part "C-USC0603K"))
    )
    (comp (ref "C51")
      (value "220PF")
      (footprint "eagle-import:C0603K")
      (libsource (lib "eagle-import") (part "C-USC0603K"))
    )
    (comp (ref "C52")
      (value "220PF")
      (footprint "eagle-import:C0603K")
      (libsource (lib "eagle-import") (part "C-USC0603K"))
    )
    (comp (ref "C53")
      (value "2.2UF")
      (footprint "eagle-import:C0603K")
      (libsource (lib "eagle-import") (part "C-USC0603K"))
    )
    (comp (ref "C54")
      (value "2.2UF")
      (footprint "eagle-import:C0603K")
      (libsource (lib "eagle-import") (part "C-USC0603K"))
    )
    (comp (ref "C55")
      (value "0.1UF")
      (footprint "eagle-import:C0603K")
      (libsource (lib "eagle-import") (part "C-USC0603K"))
    )
    (comp (ref "D1")
      (value "LED_0603")
      (footprint "eagle-import:LED_0603")
      (fields (field (name "VENDOR") "Digikey") (field (name "VENDOR_PN") "160-1438-1-ND"))
      (libsource (lib "eagle-import") (part "LED_0603"))
    )
    (comp (ref "D2")
      (value "LED_0603")
      (footprint "eagle-import:LED_0603")
      (fields (field (name "VENDOR") "Digikey") (field (name "VENDOR_PN") "160-1438-1-ND"))
      (libsource (lib "eagle-import") (part "LED_0603"))
    )
    (comp (ref "R1")
      (value "4.64K")
      (footprint "eagle-import:R0603")
      (libsource (lib "eagle-import") (part "R-US_R0603"))
    )
    (comp (ref "R2")
      (value "4.64K")
      (footprint "eagle-import:R0603")
      (libsource (lib "eagle-import") (part "R-US_R0603"))
    )
    (comp (ref "R3")
      (value "2.21K")
      (footprint "eagle-import:R0603")
      (libsource (lib "eagle-import") (part "R-US_R0603"))
    )
    (comp (ref "R4")
      (value "2.21K")
      (footprint "eagle-import:R0603")
      (libsource (lib "eagle-import") (part "R-US_R0603"))
    )
    (comp (ref "R7")
      (value "22.1K")
      (footprint "eagle-import:R0603")
      (libsource (lib "eagle-import") (part "R-US_R0603"))
    )
    (comp (ref "R8")
      (value "10K")
      (footprint "eagle-import:R0603")
      (libsource (lib "eagle-import") (part "R-US_R0603"))
    )
    (comp (ref "R9")
      (value "1K")
      (footprint "eagle-import:R0603")
      (libsource (lib "eagle-import") (part "R-US_R0603"))
    )
    (comp (ref "R10")
      (value "1K")
      (footprint "eagle-import:R0603")
      (libsource (lib "eagle-import") (part "R-US_R0603"))
    )
    (comp (ref "R11")
      (value "511")
      (footprint "eagle-import:R0603")
      (libsource (lib "eagle-import") (part "R-US_R0603"))
    )
    (comp (ref "R12")
      (value "511")
      (footprint "eagle-import:R0603")
      (libsource (lib "eagle-import") (part "R-US_R0603"))
    )
    (comp (ref "RN1")
      (value "741X163-56R")
      (footprint "eagle-import:741X163")
      (libsource (lib "eagle-import") (part "741X163-56R"))
    )
    (comp (ref "RN2")
      (value "741X163-56R")
      (footprint "eagle-import:741X163")
      (libsource (lib "eagle-import") (part "741X163-56R"))
    )
    (comp (ref "S1")
      (value "MMS-105-01-L-DV")
      (footprint "eagle-import:HEADER_2X5_2MM_TH")
      (libsource (lib "eagle-import") (part "MMS-105-01-L-DV"))
    )
    (comp (ref "U1")
      (value "TPS3828-33")
      (footprint "eagle-import:SOT23-5")
      (libsource (lib "eagle-import") (part "TPS3828-33"))
    )
    (comp (ref "U3")
      (value "TMS320F28335ZJZ")
      (footprint "eagle-import:ZJZ_PBGA176")
      (libsource (lib "eagle-import") (part "TMS320F28335ZJZ"))
    )
    (comp (ref "U4")
      (value "LIS3LV02DL")
      (footprint "eagle-import:LIS3LV02DL_LGA16")
      (libsource (lib "eagle-import") (part "LIS3LV02DL"))
    )
    (comp (ref "U5")
      (value "DS28CM00")
      (footprint "eagle-import:SOT23-5L")
      (libsource (lib "eagle-import") (part "DS28CM00"))
    )
    (comp (ref "U6")
      (value "SN74LVC2G07")
      (footprint "eagle-import:SOT23-6")
      (libsource (lib "eagle-import") (part "SN742G07LVC"))
    )
    (comp (ref "X1")
      (value "NX5032GA-30.000000MHZ")
      (footprint "eagle-import:NX5032GA")
      (libsource (lib "eagle-import") (part "NX5032GA-30.000000MHZ"))
    )
  )
  (nets
    (net (code "1") (name "+1.9V") (class "Default")
      (node (ref "C114") (pin "1") (pinfunction "1_1") (pintype "passive"))
      (node (ref "C115") (pin "1") (pinfunction "1_1") (pintype "passive"))
      (node (ref "C16") (pin "1") (pinfunction "1_1") (pintype "passive"))
      (node (ref "C17") (pin "1") (pinfunction "1_1") (pintype "passive"))
      (node (ref "C18") (pin "1") (pinfunction "1_1") (pintype "passive"))
      (node (ref "C19") (pin "1") (pinfunction "1_1") (pintype "passive"))
      (node (ref "C20") (pin "1") (pinfunction "1_1") (pintype "passive"))
      (node (ref "C21") (pin "1") (pinfunction "1_1") (pintype "passive"))
      (node (ref "C22") (pin "1") (pinfunction "1_1") (pintype "passive"))
      (node (ref "C23") (pin "1") (pinfunction "1_1") (pintype "passive"))
      (node (ref "C24") (pin "1") (pinfunction "1_1") (pintype "passive"))
      (node (ref "C25") (pin "1") (pinfunction "1_1") (pintype "passive"))
      (node (ref "C26") (pin "1") (pinfunction "1_1") (pintype "passive"))
      (node (ref "C27") (pin "1") (pinfunction "1_1") (pintype "passive"))
      (node (ref "C28") (pin "1") (pinfunction "1_1") (pintype "passive"))
      (node (ref "L2") (pin "2") (pinfunction "2_2") (pintype "passive"))
      (node (ref "R65") (pin "2") (pinfunction "2_2") (pintype "passive"))
      (node (ref "U3") (pin "D4") (pinfunction "VDD_D4") (pintype "bidirectional"))
      (node (ref "U3") (pin "D5") (pinfunction "VDD_D5") (pintype "bidirectional"))
      (node (ref "U3") (pin "D8") (pinfunction "VDD_D8") (pintype "bidirectional"))
      (node (ref "U3") (pin "D9") (pinfunction "VDD_D9") (pintype "bidirectional"))
      (node (ref "U3") (pin "E11") (pinfunction "VDD_E11") (pintype "bidirectional"))
      (node (ref "U3") (pin "F11") (pinfunction "VDD_F11") (pintype "bidirectional"))
      (node (ref "U3") (pin "F4") (pinfunction "VDD_F4") (pintype "bidirectional"))
      (node (ref "U3") (pin "H4") (pinfunction "VDD_H4") (pintype "bidirectional"))
      (node (ref "U3") (pin "J11") (pinfunction "VDD_J11") (pintype "bidirectional"))
      (node (ref "U3") (pin "J4") (pinfunction "VDD_J4") (pintype "bidirectional"))
      (node (ref "U3") (pin "K11") (pinfunction "VDD_K11") (pintype "bidirectional"))
      (node (ref "U3") (pin "L8") (pinfunction "VDD_L8") (pintype "bidirectional"))
    )
    (net (code "2") (name "+1.9VA") (class "Default")
      (node (ref "C132") (pin "1") (pinfunction "1_1") (pintype "passive"))
      (node (ref "C3") (pin "1") (pinfunction "1_1") (pintype "passive"))
      (node (ref "C4") (pin "1") (pinfunction "1_1") (pintype "passive"))
      (node (ref "E11") (pin "1") (pinfunction "1_1") (pintype "bidirectional"))
      (node (ref "R69") (pin "1") (pinfunction "1_1") (pintype "passive"))
      (node (ref "REG4") (pin "1") (pinfunction "OUT_1") (pintype "power_in"))
      (node (ref "U3") (pin "K3") (pinfunction "VDD1A18_K3") (pintype "bidirectional"))
      (node (ref "U3") (pin "L6") (pinfunction "VDD2A18_L6") (pintype "bidirectional"))
    )
    (net (code "3") (name "+3.3V") (class "Default")
      (node (ref "C10") (pin "1") (pinfunction "1_1") (pintype "passive"))
      (node (ref "C11") (pin "1") (pinfunction "1_1") (pintype "passive"))
      (node (ref "C110") (pin "1") (pinfunction "1_1") (pintype "passive"))
      (node (ref "C12") (pin "1") (pinfunction "1_1") (pintype "passive"))
      (node (ref "C13") (pin "1") (pinfunction "1_1") (pintype "passive"))
      (node (ref "C133") (pin "1") (pinfunction "1_1") (pintype "passive"))
      (node (ref "C14") (pin "1") (pinfunction "1_1") (pintype "passive"))
      (node (ref "C15") (pin "1") (pinfunction "1_1") (pintype "passive"))
      (node (ref "C30") (pin "1") (pinfunction "1_1") (pintype "passive"))
      (node (ref "C32") (pin "1") (pinfunction "1_1") (pintype "passive"))
      (node (ref "C44") (pin "1") (pinfunction "1_1") (pintype "passive"))
      (node (ref "C5") (pin "1") (pinfunction "1_1") (pintype "passive"))
      (node (ref "C55") (pin "1") (pinfunction "1_1") (pintype "passive"))
      (node (ref "C6") (pin "1") (pinfunction "1_1") (pintype "passive"))
      (node (ref "C7") (pin "1") (pinfunction "1_1") (pintype "passive"))
      (node (ref "C8") (pin "1") (pinfunction "1_1") (pintype "passive"))
      (node (ref "C9") (pin "1") (pinfunction "1_1") (pintype "passive"))
      (node (ref "L1") (pin "2") (pinfunction "2_2") (pintype "passive"))
      (node (ref "R1") (pin "2") (pinfunction "2_2") (pintype "passive"))
      (node (ref "R10") (pin "1") (pinfunction "1_1") (pintype "passive"))
      (node (ref "R11") (pin "2") (pinfunction "2_2") (pintype "passive"))
      (node (ref "R12") (pin "2") (pinfunction "2_2") (pintype "passive"))
      (node (ref "R2") (pin "2") (pinfunction "2_2") (pintype "passive"))
      (node (ref "R4") (pin "1") (pinfunction "1_1") (pintype "passive"))
      (node (ref "R60") (pin "1") (pinfunction "1_1") (pintype "passive"))
      (node (ref "R9") (pin "1") (pinfunction "1_1") (pintype "passive"))
      (node (ref "S1") (pin "1") (pinfunction "P$1_1") (pintype "bidirectional"))
      (node (ref "U1") (pin "5") (pinfunction "VDD_5") (pintype "bidirectional"))
      (node (ref "U17") (pin "4") (pinfunction "FB1_4") (pintype "input"))
      (node (ref "U18") (pin "3") (pinfunction "VDD_3") (pintype "input"))
      (node (ref "U2") (pin "14") (pinfunction "VCC_14") (pintype "power_in"))
      (node (ref "U3") (pin "A13") (pinfunction "VDDIO_A13") (pintype "bidirectional"))
      (node (ref "U3") (pin "B1") (pinfunction "VDDIO_B1") (pintype "bidirectional"))
      (node (ref "U3") (pin "D11") (pinfunction "VDDIO_D11") (pintype "bidirectional"))
      (node (ref "U3") (pin "D7") (pinfunction "VDDIO_D7") (pintype "bidirectional"))
      (node (ref "U3") (pin "E4") (pinfunction "VDDIO_E4") (pintype "bidirectional"))
      (node (ref "U3") (pin "G11") (pinfunction "VDDIO_G11") (pintype "bidirectional"))
      (node (ref "U3") (pin "G4") (pinfunction "VDDIO_G4") (pintype "bidirectional"))
      (node (ref "U3") (pin "L10") (pinfunction "VDDIO_L10") (pintype "bidirectional"))
      (node (ref "U3") (pin "L9") (pinfunction "VDD3VFL_L9") (pintype "bidirectional"))
      (node (ref "U3") (pin "N14") (pinfunction "VDDIO_N14") (pintype "bidirectional"))
      (node (ref "U4") (pin "10") (pinfunction "RES(VDD_IO)_10") (pintype "input"))
      (node (ref "U4") (pin "4") (pinfunction "VDD_IO_4") (pintype "input"))
      (node (ref "U5") (pin "5") (pinfunction "VCC_5") (pintype "bidirectional"))
      (node (ref "U6") (pin "5") (pinfunction "VCC_5") (pintype "bidirectional"))
    )
    (net (code "4") (name "+3.3VA") (class "Default")
      (node (ref "C1") (pin "1") (pinfunction "1_1") (pintype "passive"))
      (node (ref "C127") (pin "1") (pinfunction "1_1") (pintype "passive"))
      (node (ref "C128") (pin "1") (pinfunction "1_1") (pintype "passive"))
      (node (ref "C129") (pin "1") (pinfunction "1_1") (pintype "passive"))
      (node (ref "C2") (pin "1") (pinfunction "1_1") (pintype "passive"))
      (node (ref "C43") (pin "1") (pinfunction "1_1") (pintype "passive"))
      (node (ref "E10") (pin "1") (pinfunction "1_1") (pintype "bidirectional"))
      (node (ref "P3") (pin "1") (pinfunction "1_1") (pintype "bidirectional"))
      (node (ref "P4") (pin "1") (pinfunction "1_1") (pintype "bidirectional"))
      (node (ref "REG3") (pin "1") (pinfunction "OUT_1") (pintype "power_in"))
      (node (ref "REG3") (pin "2") (pinfunction "SENSE/ADJ_2") (pintype "input"))
      (node (ref "U3") (pin "K4") (pinfunction "VDDA2_K4") (pintype "bidirectional"))
      (node (ref "U3") (pin "L5") (pinfunction "VDDAIO_L5") (pintype "bidirectional"))
      (node (ref "U4") (pin "11") (pinfunction "VDD_11") (pintype "input"))
      (node (ref "U4") (pin "12") (pinfunction "RES(VDD)_12") (pintype "input"))
      (node (ref "U4") (pin "13") (pinfunction "VDD_13") (pintype "input"))
    )
    (net (code "5") (name "+5V") (class "Default")
      (node (ref "C101") (pin "1") (pinfunction "1_1") (pintype "passive"))
      (node (ref "C122") (pin "1") (pinfunction "1_1") (pintype "passive"))
      (node (ref "C123") (pin "1") (pinfunction "1_1") (pintype "passive"))
      (node (ref "C124") (pin "1") (pinfunction "1_1") (pintype "passive"))
      (node (ref "C125") (pin "1") (pinfunction "1_1") (pintype "passive"))
      (node (ref "C126") (pin "1") (pinfunction "1_1") (pintype "passive"))
      (node (ref "C130") (pin "1") (pinfunction "1_1") (pintype "passive"))
      (node (ref "C56") (pin "1") (pinfunction "1_1") (pintype "passive"))
      (node (ref "C57") (pin "1") (pinfunction "1_1") (pintype "passive"))
      (node (ref "C58") (pin "1") (pinfunction "1_1") (pintype "passive"))
      (node (ref "C59") (pin "1") (pinfunction "1_1") (pintype "passive"))
      (node (ref "C71") (pin "1") (pinfunction "1_1") (pintype "passive"))
      (node (ref "C73") (pin "1") (pinfunction "1_1") (pintype "passive"))
      (node (ref "C85") (pin "1") (pinfunction "1_1") (pintype "passive"))
      (node (ref "C96") (pin "1") (pinfunction "1_1") (pintype "passive"))
      (node (ref "E9") (pin "1") (pinfunction "1_1") (pintype "bidirectional"))
      (node (ref "P3") (pin "12") (pinfunction "1_12") (pintype "bidirectional"))
      (node (ref "P4") (pin "12") (pinfunction "1_12") (pintype "bidirectional"))
      (node (ref "R20") (pin "1") (pinfunction "1_1") (pintype "passive"))
      (node (ref "R28") (pin "2") (pinfunction "2_2") (pintype "passive"))
      (node (ref "REG2") (pin "1") (pinfunction "OUT_1") (pintype "power_in"))
      (node (ref "REG2") (pin "2") (pinfunction "SENSE/ADJ_2") (pintype "input"))
      (node (ref "REG3") (pin "5") (pinfunction "~{SHDN}_5") (pintype "input"))
      (node (ref "REG3") (pin "8") (pinfunction "IN_8") (pintype "power_in"))
      (node (ref "REG4") (pin "5") (pinfunction "~{SHDN}_5") (pintype "input"))
      (node (ref "REG4") (pin "8") (pinfunction "IN_8") (pintype "power_in"))
      (node (ref "U10") (pin "4") (pinfunction "V+_4") (pintype "power_in"))
      (node (ref "U11") (pin "11") (pinfunction "VDD_11") (pintype "bidirectional"))
      (node (ref "U11") (pin "14") (pinfunction "VDD_14") (pintype "bidirectional"))
      (node (ref "U11") (pin "3") (pinfunction "VR_3") (pintype "bidirectional"))
      (node (ref "U11") (pin "9") (pinfunction "VDD_9") (pintype "bidirectional"))
      (node (ref "U12") (pin "5") (pinfunction "REF_5") (pintype "input"))
      (node (ref "U13") (pin "5") (pinfunction "REF_5") (pintype "input"))
      (node (ref "U14") (pin "4") (pinfunction "V+_4") (pintype "power_in"))
      (node (ref "U15") (pin "4") (pinfunction "V+_4") (pintype "power_in"))
      (node (ref "U16") (pin "4") (pinfunction "V+_4") (pintype "power_in"))
      (node (ref "U7") (pin "1E") (pinfunction "VRATIO_1E") (pintype "input"))
      (node (ref "U7") (pin "2E") (pinfunction "VRATIO_2E") (pintype "input"))
      (node (ref "U7") (pin "3A") (pinfunction "AVCC_3A") (pintype "bidirectional"))
      (node (ref "U7") (pin "3B") (pinfunction "AVCC_3B") (pintype "bidirectional"))
      (node (ref "U7") (pin "6E") (pinfunction "VDD_6E") (pintype "bidirectional"))
      (node (ref "U7") (pin "7E") (pinfunction "VDD_7E") (pintype "bidirectional"))
      (node (ref "U8") (pin "4") (pinfunction "V+_4") (pintype "power_in"))
      (node (ref "U9") (pin "5") (pinfunction "REF_5") (pintype "input"))
    )
    (net (code "6") (name "+5VD") (class "Default")
      (node (ref "C111") (pin "1") (pinfunction "1_1") (pintype "passive"))
      (node (ref "C112") (pin "1") (pinfunction "1_1") (pintype "passive"))
      (node (ref "P1") (pin "7") (pinfunction "1_7") (pintype "bidirectional"))
      (node (ref "P1") (pin "8") (pinfunction "1_8") (pintype "bidirectional"))
      (node (ref "R61") (pin "1") (pinfunction "1_1") (pintype "passive"))
      (node (ref "R62") (pin "1") (pinfunction "1_1") (pintype "passive"))
      (node (ref "U17") (pin "3") (pinfunction "VIN_3") (pintype "input"))
      (node (ref "U17") (pin "9") (pinfunction "EN_2_9") (pintype "input"))
    )
    (net (code "7") (name "+10V") (class "Default")
      (node (ref "C118") (pin "1") (pinfunction "1_1") (pintype "passive"))
      (node (ref "C120") (pin "1") (pinfunction "1_1") (pintype "passive"))
      (node (ref "C121") (pin "1") (pinfunction "1_1") (pintype "passive"))
      (node (ref "C68") (pin "1") (pinfunction "1_1") (pintype "passive"))
      (node (ref "C70") (pin "1") (pinfunction "1_1") (pintype "passive"))
      (node (ref "C79") (pin "1") (pinfunction "1_1") (pintype "passive"))
      (node (ref "C80") (pin "1") (pinfunction "1_1") (pintype "passive"))
      (node (ref "C83") (pin "1") (pinfunction "1_1") (pintype "passive"))
      (node (ref "C84") (pin "1") (pinfunction "1_1") (pintype "passive"))
      (node (ref "E8") (pin "1") (pinfunction "1_1") (pintype "bidirectional"))
      (node (ref "R67") (pin "1") (pinfunction "1_1") (pintype "passive"))
      (node (ref "REG1") (pin "1") (pinfunction "OUT_1") (pintype "power_in"))
      (node (ref "REG2") (pin "5") (pinfunction "~{SHDN}_5") (pintype "input"))
      (node (ref "REG2") (pin "8") (pinfunction "IN_8") (pintype "power_in"))
      (node (ref "U12") (pin "7") (pinfunction "VS+_7") (pintype "power_in"))
      (node (ref "U13") (pin "7") (pinfunction "VS+_7") (pintype "power_in"))
      (node (ref "U9") (pin "7") (pinfunction "VS+_7") (pintype "power_in"))
    )
    (net (code "8") (name "+12V") (class "Default")
      (node (ref "C116") (pin "1") (pinfunction "1_1") (pintype "passive"))
      (node (ref "C119") (pin "1") (pinfunction "1_1") (pintype "passive"))
      (node (ref "P1") (pin "1") (pinfunction "1_1") (pintype "bidirectional"))
      (node (ref "P1") (pin "2") (pinfunction "1_2") (pintype "bidirectional"))
      (node (ref "REG1") (pin "5") (pinfunction "~{SHDN}_5") (pintype "input"))
      (node (ref "REG1") (pin "8") (pinfunction "IN_8") (pintype "power_in"))
    )
    (net (code "9") (name "ACCEL3_CS") (class "Default")
      (node (ref "U3") (pin "C1") (pinfunction "GPIO29/SCITXDA/XA19_C1") (pintype "bidirectional"))
      (node (ref "U4") (pin "6") (pinfunction "CS_6") (pintype "input"))
    )
    (net (code "10") (name "ACCEL3_RDY{slash}INT") (class "Default")
      (node (ref "U3") (pin "D1") (pinfunction "GPIO0/EPWM1A_D1") (pintype "bidirectional"))
      (node (ref "U4") (pin "1") (pinfunction "RDY/INT_1") (pintype "bidirectional"))
    )
    (net (code "11") (name "ACCELX") (class "Default")
      (node (ref "C88") (pin "2") (pinfunction "2_2") (pintype "passive"))
      (node (ref "RN1") (pin "11") (pinfunction "11_11") (pintype "passive"))
      (node (ref "U14") (pin "1") (pinfunction "OUT_1") (pintype "output"))
      (node (ref "U14") (pin "2") (pinfunction "IN-_2") (pintype "input"))
    )
    (net (code "12") (name "ACCELX_TEMP") (class "Default")
      (node (ref "RN1") (pin "13") (pinfunction "13_13") (pintype "passive"))
      (node (ref "U14") (pin "6") (pinfunction "IN-_6") (pintype "input"))
      (node (ref "U14") (pin "7") (pinfunction "OUT_7") (pintype "output"))
    )
    (net (code "13") (name "ACCELY") (class "Default")
      (node (ref "C90") (pin "2") (pinfunction "2_2") (pintype "passive"))
      (node (ref "RN2") (pin "7") (pinfunction "7_7") (pintype "passive"))
      (node (ref "U10") (pin "13") (pinfunction "IN-_13") (pintype "input"))
      (node (ref "U10") (pin "14") (pinfunction "OUT_14") (pintype "output"))
    )
    (net (code "14") (name "ACCELY_TEMP") (class "Default")
      (node (ref "RN2") (pin "8") (pinfunction "8_8") (pintype "passive"))
      (node (ref "U10") (pin "8") (pinfunction "OUT_8") (pintype "output"))
      (node (ref "U10") (pin "9") (pinfunction "IN-_9") (pintype "input"))
    )
    (net (code "15") (name "ACCELZ") (class "Default")
      (node (ref "C74") (pin "2") (pinfunction "2_2") (pintype "passive"))
      (node (ref "RN2") (pin "5") (pinfunction "5_5") (pintype "passive"))
      (node (ref "U10") (pin "1") (pinfunction "OUT_1") (pintype "output"))
      (node (ref "U10") (pin "2") (pinfunction "IN-_2") (pintype "input"))
    )
    (net (code "16") (name "ACCELZ_TEMP") (class "Default")
      (node (ref "RN2") (pin "6") (pinfunction "6_6") (pintype "passive"))
      (node (ref "U10") (pin "6") (pinfunction "IN-_6") (pintype "input"))
      (node (ref "U10") (pin "7") (pinfunction "OUT_7") (pintype "output"))
    )
    (net (code "17") (name "AGND") (class "Default")
      (node (ref "C1") (pin "2") (pinfunction "2_2") (pintype "passive"))
      (node (ref "C100") (pin "2") (pinfunction "2_2") (pintype "passive"))
      (node (ref "C101") (pin "2") (pinfunction "2_2") (pintype "passive"))
      (node (ref "C102") (pin "2") (pinfunction "2_2") (pintype "passive"))
      (node (ref "C103") (pin "2") (pinfunction "2_2") (pintype "passive"))
      (node (ref "C105") (pin "2") (pinfunction "2_2") (pintype "passive"))
      (node (ref "C107") (pin "2") (pinfunction "2_2") (pintype "passive"))
      (node (ref "C109") (pin "2") (pinfunction "2_2") (pintype "passive"))
      (node (ref "C116") (pin "2") (pinfunction "2_2") (pintype "passive"))
      (node (ref "C118") (pin "2") (pinfunction "2_2") (pintype "passive"))
      (node (ref "C119") (pin "2") (pinfunction "2_2") (pintype "passive"))
      (node (ref "C120") (pin "2") (pinfunction "2_2") (pintype "passive"))
      (node (ref "C121") (pin "2") (pinfunction "2_2") (pintype "passive"))
      (node (ref "C123") (pin "2") (pinfunction "2_2") (pintype "passive"))
      (node (ref "C124") (pin "2") (pinfunction "2_2") (pintype "passive"))
      (node (ref "C125") (pin "2") (pinfunction "2_2") (pintype "passive"))
      (node (ref "C126") (pin "2") (pinfunction "2_2") (pintype "passive"))
      (node (ref "C128") (pin "2") (pinfunction "2_2") (pintype "passive"))
      (node (ref "C129") (pin "2") (pinfunction "2_2") (pintype "passive"))
      (node (ref "C130") (pin "2") (pinfunction "2_2") (pintype "passive"))
      (node (ref "C132") (pin "2") (pinfunction "2_2") (pintype "passive"))
      (node (ref "C2") (pin "2") (pinfunction "2_2") (pintype "passive"))
      (node (ref "C3") (pin "2") (pinfunction "2_2") (pintype "passive"))
      (node (ref "C35") (pin "2") (pinfunction "2_2") (pintype "passive"))
      (node (ref "C36") (pin "2") (pinfunction "2_2") (pintype "passive"))
      (node (ref "C37") (pin "2") (pinfunction "2_2") (pintype "passive"))
      (node (ref "C38") (pin "2") (pinfunction "2_2") (pintype "passive"))
      (node (ref "C39") (pin "2") (pinfunction "2_2") (pintype "passive"))
      (node (ref "C4") (pin "2") (pinfunction "2_2") (pintype "passive"))
      (node (ref "C40") (pin "2") (pinfunction "2_2") (pintype "passive"))
      (node (ref "C41") (pin "2") (pinfunction "2_2") (pintype "passive"))
      (node (ref "C42") (pin "2") (pinfunction "2_2") (pintype "passive"))
      (node (ref "C43") (pin "2") (pinfunction "2_2") (pintype "passive"))
      (node (ref "C45") (pin "2") (pinfunction "2_2") (pintype "passive"))
      (node (ref "C46") (pin "2") (pinfunction "2_2") (pintype "passive"))
      (node (ref "C47") (pin "2") (pinfunction "2_2") (pintype "passive"))
      (node (ref "C48") (pin "2") (pinfunction "2_2") (pintype "passive"))
      (node (ref "C49") (pin "2") (pinfunction "2_2") (pintype "passive"))
      (node (ref "C50") (pin "2") (pinfunction "2_2") (pintype "passive"))
      (node (ref "C51") (pin "2") (pinfunction "2_2") (pintype "passive"))
      (node (ref "C52") (pin "2") (pinfunction "2_2") (pintype "passive"))
      (node (ref "C53") (pin "2") (pinfunction "2_2") (pintype "passive"))
      (node (ref "C54") (pin "2") (pinfunction "2_2") (pintype "passive"))
      (node (ref "C56") (pin "2") (pinfunction "2_2") (pintype "passive"))
      (node (ref "C57") (pin "2") (pinfunction "2_2") (pintype "passive"))
      (node (ref "C58") (pin "2") (pinfunction "2_2") (pintype "passive"))
      (node (ref "C59") (pin "2") (pinfunction "2_2") (pintype "passive"))
      (node (ref "C63") (pin "2") (pinfunction "2_2") (pintype "passive"))
      (node (ref "C65") (pin "2") (pinfunction "2_2") (pintype "passive"))
      (node (ref "C66") (pin "2") (pinfunction "2_2") (pintype "passive"))
      (node (ref "C67") (pin "2") (pinfunction "2_2") (pintype "passive"))
      (node (ref "C68") (pin "2") (pinfunction "2_2") (pintype "passive"))
      (node (ref "C69") (pin "1") (pinfunction "1_1") (pintype "passive"))
      (node (ref "C70") (pin "2") (pinfunction "2_2") (pintype "passive"))
      (node (ref "C71") (pin "2") (pinfunction "2_2") (pintype "passive"))
      (node (ref "C73") (pin "2") (pinfunction "2_2") (pintype "passive"))
      (node (ref "C75") (pin "2") (pinfunction "2_2") (pintype "passive"))
      (node (ref "C76") (pin "2") (pinfunction "2_2") (pintype "passive"))
      (node (ref "C77") (pin "2") (pinfunction "2_2") (pintype "passive"))
      (node (ref "C78") (pin "2") (pinfunction "2_2") (pintype "passive"))
      (node (ref "C79") (pin "2") (pinfunction "2_2") (pintype "passive"))
      (node (ref "C80") (pin "2") (pinfunction "2_2") (pintype "passive"))
      (node (ref "C81") (pin "1") (pinfunction "1_1") (pintype "passive"))
      (node (ref "C82") (pin "1") (pinfunction "1_1") (pintype "passive"))
      (node (ref "C83") (pin "2") (pinfunction "2_2") (pintype "passive"))
      (node (ref "C84") (pin "2") (pinfunction "2_2") (pintype "passive"))
      (node (ref "C85") (pin "2") (pinfunction "2_2") (pintype "passive"))
      (node (ref "C89") (pin "2") (pinfunction "2_2") (pintype "passive"))
      (node (ref "C91") (pin "2") (pinfunction "2_2") (pintype "passive"))
      (node (ref "C92") (pin "2") (pinfunction "2_2") (pintype "passive"))
      (node (ref "C93") (pin "2") (pinfunction "2_2") (pintype "passive"))
      (node (ref "C94") (pin "2") (pinfunction "2_2") (pintype "passive"))
      (node (ref "C95") (pin "2") (pinfunction "2_2") (pintype "passive"))
      (node (ref "C96") (pin "2") (pinfunction "2_2") (pintype "passive"))
      (node (ref "C98") (pin "2") (pinfunction "2_2") (pintype "passive"))
      (node (ref "E1") (pin "1") (pinfunction "1_1") (pintype "bidirectional"))
      (node (ref "P1") (pin "3") (pinfunction "1_3") (pintype "bidirectional"))
      (node (ref "P1") (pin "4") (pinfunction "1_4") (pintype "bidirectional"))
      (node (ref "P3") (pin "11") (pinfunction "1_11") (pintype "bidirectional"))
      (node (ref "P3") (pin "2") (pinfunction "1_2") (pintype "bidirectional"))
      (node (ref "P4") (pin "11") (pinfunction "1_11") (pintype "bidirectional"))
      (node (ref "P4") (pin "2") (pinfunction "1_2") (pintype "bidirectional"))
      (node (ref "R17") (pin "2") (pinfunction "2_2") (pintype "passive"))
      (node (ref "R18") (pin "1") (pinfunction "1_1") (pintype "passive"))
      (node (ref "R19") (pin "1") (pinfunction "1_1") (pintype "passive"))
      (node (ref "R21") (pin "1") (pinfunction "1_1") (pintype "passive"))
      (node (ref "R27") (pin "1") (pinfunction "1_1") (pintype "passive"))
      (node (ref "R29") (pin "1") (pinfunction "1_1") (pintype "passive"))
      (node (ref "R30") (pin "2") (pinfunction "2_2") (pintype "passive"))
      (node (ref "R41") (pin "1") (pinfunction "1_1") (pintype "passive"))
      (node (ref "R42") (pin "1") (pinfunction "1_1") (pintype "passive"))
      (node (ref "R43") (pin "2") (pinfunction "2_2") (pintype "passive"))
      (node (ref "R44") (pin "2") (pinfunction "2_2") (pintype "passive"))
      (node (ref "R51") (pin "2") (pinfunction "2_2") (pintype "passive"))
      (node (ref "R52") (pin "2") (pinfunction "2_2") (pintype "passive"))
      (node (ref "R59") (pin "2") (pinfunction "2_2") (pintype "passive"))
      (node (ref "R68") (pin "2") (pinfunction "2_2") (pintype "passive"))
      (node (ref "R7") (pin "1") (pinfunction "1_1") (pintype "passive"))
      (node (ref "R70") (pin "2") (pinfunction "2_2") (pintype "passive"))
      (node (ref "REG1") (pin "4") (pinfunction "GND_4") (pintype "power_in"))
      (node (ref "REG2") (pin "4") (pinfunction "GND_4") (pintype "power_in"))
      (node (ref "REG3") (pin "4") (pinfunction "GND_4") (pintype "power_in"))
      (node (ref "REG4") (pin "4") (pinfunction "GND_4") (pintype "power_in"))
      (node (ref "U10") (pin "11") (pinfunction "V-_11") (pintype "power_in"))
      (node (ref "U11") (pin "18") (pinfunction "GND_18") (pintype "bidirectional"))
      (node (ref "U11") (pin "19") (pinfunction "GND_19") (pintype "bidirectional"))
      (node (ref "U11") (pin "2") (pinfunction "GND_2") (pintype "bidirectional"))
      (node (ref "U11") (pin "5") (pinfunction "GND_5") (pintype "bidirectional"))
      (node (ref "U11") (pin "6") (pinfunction "GND_6") (pintype "bidirectional"))
      (node (ref "U12") (pin "4") (pinfunction "VS-_4") (pintype "power_in"))
      (node (ref "U13") (pin "4") (pinfunction "VS-_4") (pintype "power_in"))
      (node (ref "U14") (pin "11") (pinfunction "V-_11") (pintype "power_in"))
      (node (ref "U15") (pin "11") (pinfunction "V-_11") (pintype "power_in"))
      (node (ref "U16") (pin "11") (pinfunction "V-_11") (pintype "power_in"))
      (node (ref "U3") (pin "L4") (pinfunction "VSS1AGND_L4") (pintype "bidirectional"))
      (node (ref "U3") (pin "N1") (pinfunction "VSSAIO_N1") (pintype "bidirectional"))
      (node (ref "U3") (pin "N2") (pinfunction "ADCLO_N2") (pintype "bidirectional"))
      (node (ref "U3") (pin "P1") (pinfunction "VSSA2_P1") (pintype "bidirectional"))
      (node (ref "U3") (pin "P2") (pinfunction "VSS2AGND_P2") (pintype "bidirectional"))
      (node (ref "U3") (pin "P7") (pinfunction "ADCREFIN_P7") (pintype "bidirectional"))
      (node (ref "U4") (pin "14") (pinfunction "GND_14") (pintype "input"))
      (node (ref "U4") (pin "15") (pinfunction "RES(GND)_15") (pintype "input"))
      (node (ref "U4") (pin "16") (pinfunction "GND_16") (pintype "input"))
      (node (ref "U4") (pin "8") (pinfunction "CK_8") (pintype "input"))
      (node (ref "U4") (pin "9") (pinfunction "GND_9") (pintype "input"))
      (node (ref "U7") (pin "1F") (pinfunction "AGND_1F") (pintype "bidirectional"))
      (node (ref "U7") (pin "2G") (pinfunction "AGND_2G") (pintype "bidirectional"))
      (node (ref "U7") (pin "6G") (pinfunction "PGND_6G") (pintype "bidirectional"))
      (node (ref "U7") (pin "7F") (pinfunction "PGND_7F") (pintype "bidirectional"))
      (node (ref "U8") (pin "11") (pinfunction "V-_11") (pintype "power_in"))
      (node (ref "U9") (pin "4") (pinfunction "VS-_4") (pintype "power_in"))
    )
    (net (code "18") (name "CAN_RX") (class "Default")
      (node (ref "U18") (pin "4") (pinfunction "R_4") (pintype "output"))
      (node (ref "U3") (pin "C2") (pinfunction "GPIO30/CANRXA/XA18_C2") (pintype "bidirectional"))
    )
    (net (code "19") (name "CAN_TX") (class "Default")
      (node (ref "U18") (pin "1") (pinfunction "D_1") (pintype "input"))
      (node (ref "U3") (pin "B2") (pinfunction "GPIO31/CANTXA/XA17_B2") (pintype "bidirectional"))
    )
    (net (code "20") (name "DGND") (class "Default")
      (node (ref "C10") (pin "2") (pinfunction "2_2") (pintype "passive"))
      (node (ref "C11") (pin "2") (pinfunction "2_2") (pintype "passive"))
      (node (ref "C110") (pin "2") (pinfunction "2_2") (pintype "passive"))
      (node (ref "C111") (pin "2") (pinfunction "2_2") (pintype "passive"))
      (node (ref "C112") (pin "2") (pinfunction "2_2") (pintype "passive"))
      (node (ref "C113") (pin "2") (pinfunction "2_2") (pintype "passive"))
      (node (ref "C115") (pin "2") (pinfunction "2_2") (pintype "passive"))
      (node (ref "C12") (pin "2") (pinfunction "2_2") (pintype "passive"))
      (node (ref "C13") (pin "2") (pinfunction "2_2") (pintype "passive"))
      (node (ref "C133") (pin "2") (pinfunction "2_2") (pintype "passive"))
      (node (ref "C14") (pin "2") (pinfunction "2_2") (pintype "passive"))
      (node (ref "C15") (pin "2") (pinfunction "2_2") (pintype "passive"))
      (node (ref "C16") (pin "2") (pinfunction "2_2") (pintype "passive"))
      (node (ref "C17") (pin "2") (pinfunction "2_2") (pintype "passive"))
      (node (ref "C18") (pin "2") (pinfunction "2_2") (pintype "passive"))
      (node (ref "C19") (pin "2") (pinfunction "2_2") (pintype "passive"))
      (node (ref "C20") (pin "2") (pinfunction "2_2") (pintype "passive"))
      (node (ref "C21") (pin "2") (pinfunction "2_2") (pintype "passive"))
      (node (ref "C22") (pin "2") (pinfunction "2_2") (pintype "passive"))
      (node (ref "C23") (pin "2") (pinfunction "2_2") (pintype "passive"))
      (node (ref "C24") (pin "2") (pinfunction "2_2") (pintype "passive"))
      (node (ref "C25") (pin "2") (pinfunction "2_2") (pintype "passive"))
      (node (ref "C26") (pin "2") (pinfunction "2_2") (pintype "passive"))
      (node (ref "C27") (pin "2") (pinfunction "2_2") (pintype "passive"))
      (node (ref "C28") (pin "2") (pinfunction "2_2") (pintype "passive"))
      (node (ref "C29") (pin "2") (pinfunction "2_2") (pintype "passive"))
      (node (ref "C30") (pin "2") (pinfunction "2_2") (pintype "passive"))
      (node (ref "C31") (pin "2") (pinfunction "2_2") (pintype "passive"))
      (node (ref "C32") (pin "2") (pinfunction "2_2") (pintype "passive"))
      (node (ref "C33") (pin "2") (pinfunction "2_2") (pintype "passive"))
      (node (ref "C34") (pin "2") (pinfunction "2_2") (pintype "passive"))
      (node (ref "C44") (pin "2") (pinfunction "2_2") (pintype "passive"))
      (node (ref "C5") (pin "2") (pinfunction "2_2") (pintype "passive"))
      (node (ref "C55") (pin "2") (pinfunction "2_2") (pintype "passive"))
      (node (ref "C6") (pin "2") (pinfunction "2_2") (pintype "passive"))
      (node (ref "C7") (pin "2") (pinfunction "2_2") (pintype "passive"))
      (node (ref "C8") (pin "2") (pinfunction "2_2") (pintype "passive"))
      (node (ref "C9") (pin "2") (pinfunction "2_2") (pintype "passive"))
      (node (ref "D14") (pin "3") (pinfunction "3_3") (pintype "passive"))
      (node (ref "P1") (pin "5") (pinfunction "1_5") (pintype "bidirectional"))
      (node (ref "P1") (pin "6") (pinfunction "1_6") (pintype "bidirectional"))
      (node (ref "R3") (pin "2") (pinfunction "2_2") (pintype "passive"))
      (node (ref "R63") (pin "2") (pinfunction "2_2") (pintype "passive"))
      (node (ref "R64") (pin "2") (pinfunction "2_2") (pintype "passive"))
      (node (ref "R66") (pin "1") (pinfunction "1_1") (pintype "passive"))
      (node (ref "R71") (pin "1") (pinfunction "1_1") (pintype "passive"))
      (node (ref "R8") (pin "1") (pinfunction "1_1") (pintype "passive"))
      (node (ref "S1") (pin "10") (pinfunction "1_10") (pintype "bidirectional"))
      (node (ref "S1") (pin "9") (pinfunction "1_9") (pintype "bidirectional"))
      (node (ref "U1") (pin "2") (pinfunction "GND_2") (pintype "bidirectional"))
      (node (ref "U17") (pin "8") (pinfunction "GND_8") (pintype "input"))
      (node (ref "U17") (pin "PWRPAD") (pinfunction "PWRPAD_PWRPAD") (pintype "power_in"))
      (node (ref "U18") (pin "2") (pinfunction "VSS_2") (pintype "input"))
      (node (ref "U2") (pin "13") (pinfunction "RXP_13") (pintype "input"))
      (node (ref "U2") (pin "6") (pinfunction "SRL_6") (pintype "input"))
      (node (ref "U2") (pin "7") (pinfunction "GND_7") (pintype "power_in"))
      (node (ref "U2") (pin "8") (pinfunction "TXP_8") (pintype "input"))
      (node (ref "U3") (pin "A1") (pinfunction "VSS_A1") (pintype "bidirectional"))
      (node (ref "U3") (pin "A14") (pinfunction "VSS_A14") (pintype "bidirectional"))
      (node (ref "U3") (pin "A2") (pinfunction "VSS_A2") (pintype "bidirectional"))
      (node (ref "U3") (pin "B14") (pinfunction "VSS_B14") (pintype "bidirectional"))
      (node (ref "U3") (pin "F6") (pinfunction "VSS_F6") (pintype "bidirectional"))
      (node (ref "U3") (pin "F7") (pinfunction "VSS_F7") (pintype "bidirectional"))
      (node (ref "U3") (pin "F8") (pinfunction "VSS_F8") (pintype "bidirectional"))
      (node (ref "U3") (pin "F9") (pinfunction "VSS_F9") (pintype "bidirectional"))
      (node (ref "U3") (pin "G13") (pinfunction "XCLKIN_G13") (pintype "bidirectional"))
      (node (ref "U3") (pin "G6") (pinfunction "VSS_G6") (pintype "bidirectional"))
      (node (ref "U3") (pin "G7") (pinfunction "VSS_G7") (pintype "bidirectional"))
      (node (ref "U3") (pin "G8") (pinfunction "VSS_G8") (pintype "bidirectional"))
      (node (ref "U3") (pin "G9") (pinfunction "VSS_G9") (pintype "bidirectional"))
      (node (ref "U3") (pin "H6") (pinfunction "VSS_H6") (pintype "bidirectional"))
      (node (ref "U3") (pin "H7") (pinfunction "VSS_H7") (pintype "bidirectional"))
      (node (ref "U3") (pin "H8") (pinfunction "VSS_H8") (pintype "bidirectional"))
      (node (ref "U3") (pin "H9") (pinfunction "VSS_H9") (pintype "bidirectional"))
      (node (ref "U3") (pin "J6") (pinfunction "VSS_J6") (pintype "bidirectional"))
      (node (ref "U3") (pin "J7") (pinfunction "VSS_J7") (pintype "bidirectional"))
      (node (ref "U3") (pin "J8") (pinfunction "VSS_J8") (pintype "bidirectional"))
      (node (ref "U3") (pin "J9") (pinfunction "VSS_J9") (pintype "bidirectional"))
      (node (ref "U3") (pin "P13") (pinfunction "VSS_P13") (pintype "bidirectional"))
      (node (ref "U3") (pin "P14") (pinfunction "VSS_P14") (pintype "bidirectional"))
      (node (ref "U5") (pin "2") (pinfunction "GND_2") (pintype "bidirectional"))
      (node (ref "U6") (pin "2") (pinfunction "GND_2") (pintype "bidirectional"))
    )
    (net (code "21") (name "EMU0") (class "Default")
      (node (ref "R1") (pin "1") (pinfunction "1_1") (pintype "passive"))
      (node (ref "S1") (pin "7") (pinfunction "1_7") (pintype "bidirectional"))
      (node (ref "U3") (pin "N7") (pinfunction "EMU0_N7") (pintype "bidirectional"))
    )
    (net (code "22") (name "EMU1") (class "Default")
      (node (ref "R2") (pin "1") (pinfunction "1_1") (pintype "passive"))
      (node (ref "S1") (pin "8") (pinfunction "1_8") (pintype "bidirectional"))
      (node (ref "U3") (pin "P8") (pinfunction "EMU1_P8") (pintype "bidirectional"))
    )
    (net (code "23") (name "GYROX") (class "Default")
      (node (ref "C97") (pin "2") (pinfunction "2_2") (pintype "passive"))
      (node (ref "RN1") (pin "10") (pinfunction "10_10") (pintype "passive"))
      (node (ref "U14") (pin "13") (pinfunction "IN-_13") (pintype "input"))
      (node (ref "U14") (pin "14") (pinfunction "OUT_14") (pintype "output"))
    )
    (net (code "24") (name "GYROX_TEMP") (class "Default")
      (node (ref "RN1") (pin "12") (pinfunction "12_12") (pintype "passive"))
      (node (ref "U16") (pin "1") (pinfunction "OUT_1") (pintype "output"))
      (node (ref "U16") (pin "2") (pinfunction "IN-_2") (pintype "input"))
    )
    (net (code "25") (name "GYROY") (class "Default")
      (node (ref "C99") (pin "2") (pinfunction "2_2") (pintype "passive"))
      (node (ref "RN2") (pin "3") (pinfunction "3_3") (pintype "passive"))
      (node (ref "U15") (pin "6") (pinfunction "IN-_6") (pintype "input"))
      (node (ref "U15") (pin "7") (pinfunction "OUT_7") (pintype "output"))
    )
    (net (code "26") (name "GYROY_TEMP") (class "Default")
      (node (ref "RN2") (pin "4") (pinfunction "4_4") (pintype "passive"))
      (node (ref "U15") (pin "8") (pinfunction "OUT_8") (pintype "output"))
      (node (ref "U15") (pin "9") (pinfunction "IN-_9") (pintype "input"))
    )
    (net (code "27") (name "GYROZ") (class "Default")
      (node (ref "C62") (pin "2") (pinfunction "2_2") (pintype "passive"))
      (node (ref "RN2") (pin "1") (pinfunction "1_1") (pintype "passive"))
      (node (ref "U8") (pin "6") (pinfunction "IN-_6") (pintype "input"))
      (node (ref "U8") (pin "7") (pinfunction "OUT_7") (pintype "output"))
    )
    (net (code "28") (name "GYROZ_TEMP") (class "Default")
      (node (ref "RN1") (pin "16") (pinfunction "16_16") (pintype "passive"))
      (node (ref "U8") (pin "8") (pinfunction "OUT_8") (pintype "output"))
      (node (ref "U8") (pin "9") (pinfunction "IN-_9") (pintype "input"))
    )
    (net (code "29") (name "ID_SCL") (class "Default")
      (node (ref "R9") (pin "2") (pinfunction "2_2") (pintype "passive"))
      (node (ref "U3") (pin "P12") (pinfunction "GPIO33/SCLA/EPWMSYNCO/~{ADCSOCBO}_P12") (pintype "bidirectional"))
      (node (ref "U5") (pin "1") (pinfunction "SCL_1") (pintype "bidirectional"))
    )
    (net (code "30") (name "ID_SDA") (class "Default")
      (node (ref "R10") (pin "2") (pinfunction "2_2") (pintype "passive"))
      (node (ref "U3") (pin "M11") (pinfunction "GPIO32/SDAA/EPWMSYNCI/~{ADCSOCAO}_M11") (pintype "bidirectional"))
      (node (ref "U5") (pin "3") (pinfunction "SDA_3") (pintype "bidirectional"))
    )
    (net (code "31") (name "IMU_422A") (class "Default")
      (node (ref "P1") (pin "18") (pinfunction "1_18") (pintype "bidirectional"))
      (node (ref "R6") (pin "1") (pinfunction "1_1") (pintype "passive"))
      (node (ref "U2") (pin "9") (pinfunction "Y/TX+_9") (pintype "output"))
    )
    (net (code "32") (name "IMU_422B") (class "Default")
      (node (ref "P1") (pin "17") (pinfunction "1_17") (pintype "bidirectional"))
      (node (ref "R6") (pin "2") (pinfunction "2_2") (pintype "passive"))
      (node (ref "U2") (pin "10") (pinfunction "Z/TX-_10") (pintype "output"))
    )
    (net (code "33") (name "IMU_422Y") (class "Default")
      (node (ref "P1") (pin "15") (pinfunction "1_15") (pintype "bidirectional"))
      (node (ref "R5") (pin "2") (pinfunction "2_2") (pintype "passive"))
      (node (ref "U2") (pin "12") (pinfunction "A/RX+_12") (pintype "input"))
    )
    (net (code "34") (name "IMU_422Z") (class "Default")
      (node (ref "P1") (pin "16") (pinfunction "1_16") (pintype "bidirectional"))
      (node (ref "R5") (pin "1") (pinfunction "1_1") (pintype "passive"))
      (node (ref "U2") (pin "11") (pinfunction "B/RX-_11") (pintype "input"))
    )
    (net (code "35") (name "IMU_CANH") (class "Default")
      (node (ref "D14") (pin "1") (pinfunction "1_1") (pintype "passive"))
      (node (ref "P1") (pin "20") (pinfunction "1_20") (pintype "bidirectional"))
      (node (ref "R72") (pin "2") (pinfunction "2_2") (pintype "passive"))
      (node (ref "U18") (pin "7") (pinfunction "CANH_7") (pintype "bidirectional"))
    )
    (net (code "36") (name "IMU_CANL") (class "Default")
      (node (ref "D14") (pin "2") (pinfunction "2_2") (pintype "passive"))
      (node (ref "P1") (pin "19") (pinfunction "1_19") (pintype "bidirectional"))
      (node (ref "R72") (pin "1") (pinfunction "1_1") (pintype "passive"))
      (node (ref "U18") (pin "6") (pinfunction "CANL_6") (pintype "bidirectional"))
    )
    (net (code "37") (name "MAGX") (class "Default")
      (node (ref "C106") (pin "2") (pinfunction "2_2") (pintype "passive"))
      (node (ref "RN2") (pin "2") (pinfunction "2_2") (pintype "passive"))
      (node (ref "U15") (pin "13") (pinfunction "IN-_13") (pintype "input"))
      (node (ref "U15") (pin "14") (pinfunction "OUT_14") (pintype "output"))
    )
    (net (code "38") (name "MAGY") (class "Default")
      (node (ref "C104") (pin "2") (pinfunction "2_2") (pintype "passive"))
      (node (ref "RN1") (pin "14") (pinfunction "14_14") (pintype "passive"))
      (node (ref "U16") (pin "6") (pinfunction "IN-_6") (pintype "input"))
      (node (ref "U16") (pin "7") (pinfunction "OUT_7") (pintype "output"))
    )
    (net (code "39") (name "MAGZ") (class "Default")
      (node (ref "C108") (pin "2") (pinfunction "2_2") (pintype "passive"))
      (node (ref "RN1") (pin "9") (pinfunction "9_9") (pintype "passive"))
      (node (ref "U16") (pin "8") (pinfunction "OUT_8") (pintype "output"))
      (node (ref "U16") (pin "9") (pinfunction "IN-_9") (pintype "input"))
    )
    (net (code "40") (name "MAG_RESET") (class "Default")
      (node (ref "P3") (pin "3") (pinfunction "1_3") (pintype "bidirectional"))
      (node (ref "P4") (pin "3") (pinfunction "1_3") (pintype "bidirectional"))
      (node (ref "R8") (pin "2") (pinfunction "2_2") (pintype "passive"))
      (node (ref "U3") (pin "G1") (pinfunction "GPIO9/EPWM5B/SCITXDB/ECAP3_G1") (pintype "bidirectional"))
    )
    (net (code "41") (name "Net-(C60-Pad1)") (class "Default")
      (node (ref "C60") (pin "1") (pinfunction "1_1") (pintype "passive"))
      (node (ref "U7") (pin "5A") (pinfunction "CP1_5A") (pintype "bidirectional"))
      (node (ref "U7") (pin "5B") (pinfunction "CP1_5B") (pintype "bidirectional"))
    )
    (net (code "42") (name "Net-(C60-Pad2)") (class "Default")
      (node (ref "C60") (pin "2") (pinfunction "2_2") (pintype "passive"))
      (node (ref "U7") (pin "4A") (pinfunction "CP2_4A") (pintype "bidirectional"))
      (node (ref "U7") (pin "4B") (pinfunction "CP2_4B") (pintype "bidirectional"))
    )
    (net (code "43") (name "Net-(C61-Pad1)") (class "Default")
      (node (ref "C61") (pin "1") (pinfunction "1_1") (pintype "passive"))
      (node (ref "R13") (pin "2") (pinfunction "2_2") (pintype "passive"))
      (node (ref "R16") (pin "2") (pinfunction "2_2") (pintype "passive"))
      (node (ref "U7") (pin "1B") (pinfunction "RATEOUT_1B") (pintype "output"))
      (node (ref "U7") (pin "2A") (pinfunction "RATEOUT_2A") (pintype "output"))
    )
    (net (code "44") (name "Net-(C61-Pad2)") (class "Default")
      (node (ref "C61") (pin "2") (pinfunction "2_2") (pintype "passive"))
      (node (ref "R16") (pin "1") (pinfunction "1_1") (pintype "passive"))
      (node (ref "U7") (pin "1C") (pinfunction "SUMJ_1C") (pintype "bidirectional"))
      (node (ref "U7") (pin "2C") (pinfunction "SUMJ_2C") (pintype "bidirectional"))
    )
    (net (code "45") (name "Net-(C62-Pad1)") (class "Default")
      (node (ref "C62") (pin "1") (pinfunction "1_1") (pintype "passive"))
      (node (ref "R14") (pin "1") (pinfunction "1_1") (pintype "passive"))
      (node (ref "R15") (pin "2") (pinfunction "2_2") (pintype "passive"))
    )
    (net (code "46") (name "Net-(C64-Pad1)") (class "Default")
      (node (ref "C64") (pin "1") (pinfunction "1_1") (pintype "passive"))
      (node (ref "U7") (pin "6C") (pinfunction "CP3_6C") (pintype "bidirectional"))
      (node (ref "U7") (pin "7C") (pinfunction "CP3_7C") (pintype "bidirectional"))
    )
    (net (code "47") (name "Net-(C64-Pad2)") (class "Default")
      (node (ref "C64") (pin "2") (pinfunction "2_2") (pintype "passive"))
      (node (ref "U7") (pin "6A") (pinfunction "CP4_6A") (pintype "bidirectional"))
      (node (ref "U7") (pin "7B") (pinfunction "CP4_7B") (pintype "bidirectional"))
    )
    (net (code "48") (name "Net-(C65-Pad1)") (class "Default")
      (node (ref "C65") (pin "1") (pinfunction "1_1") (pintype "passive"))
      (node (ref "U7") (pin "6D") (pinfunction "CP5_6D") (pintype "bidirectional"))
      (node (ref "U7") (pin "7D") (pinfunction "CP5_7D") (pintype "bidirectional"))
    )
    (net (code "49") (name "Net-(C74-Pad1)") (class "Default")
      (node (ref "C74") (pin "1") (pinfunction "1_1") (pintype "passive"))
      (node (ref "R24") (pin "2") (pinfunction "2_2") (pintype "passive"))
      (node (ref "R25") (pin "2") (pinfunction "2_2") (pintype "passive"))
      (node (ref "R27") (pin "2") (pinfunction "2_2") (pintype "passive"))
    )
    (net (code "50") (name "Net-(C88-Pad1)") (class "Default")
      (node (ref "C88") (pin "1") (pinfunction "1_1") (pintype "passive"))
      (node (ref "R34") (pin "2") (pinfunction "2_2") (pintype "passive"))
      (node (ref "R35") (pin "2") (pinfunction "2_2") (pintype "passive"))
      (node (ref "R41") (pin "2") (pinfunction "2_2") (pintype "passive"))
    )
    (net (code "51") (name "Net-(C90-Pad1)") (class "Default")
      (node (ref "C90") (pin "1") (pinfunction "1_1") (pintype "passive"))
      (node (ref "R37") (pin "2") (pinfunction "2_2") (pintype "passive"))
      (node (ref "R38") (pin "2") (pinfunction "2_2") (pintype "passive"))
      (node (ref "R42") (pin "2") (pinfunction "2_2") (pintype "passive"))
    )
    (net (code "52") (name "Net-(C97-Pad1)") (class "Default")
      (node (ref "C97") (pin "1") (pinfunction "1_1") (pintype "passive"))
      (node (ref "R47") (pin "1") (pinfunction "1_1") (pintype "passive"))
      (node (ref "R48") (pin "2") (pinfunction "2_2") (pintype "passive"))
    )
    (net (code "53") (name "Net-(C99-Pad1)") (class "Default")
      (node (ref "C99") (pin "1") (pinfunction "1_1") (pintype "passive"))
      (node (ref "R49") (pin "1") (pinfunction "1_1") (pintype "passive"))
      (node (ref "R50") (pin "2") (pinfunction "2_2") (pintype "passive"))
    )
    (net (code "54") (name "Net-(C104-Pad1)") (class "Default")
      (node (ref "C104") (pin "1") (pinfunction "1_1") (pintype "passive"))
      (node (ref "R53") (pin "1") (pinfunction "1_1") (pintype "passive"))
      (node (ref "R54") (pin "2") (pinfunction "2_2") (pintype "passive"))
    )
    (net (code "55") (name "Net-(C106-Pad1)") (class "Default")
      (node (ref "C106") (pin "1") (pinfunction "1_1") (pintype "passive"))
      (node (ref "R55") (pin "1") (pinfunction "1_1") (pintype "passive"))
      (node (ref "R56") (pin "2") (pinfunction "2_2") (pintype "passive"))
    )
    (net (code "56") (name "Net-(C108-Pad1)") (class "Default")
      (node (ref "C108") (pin "1") (pinfunction "1_1") (pintype "passive"))
      (node (ref "R57") (pin "1") (pinfunction "1_1") (pintype "passive"))
      (node (ref "R58") (pin "2") (pinfunction "2_2") (pintype "passive"))
    )
    (net (code "57") (name "Net-(D1-PadA)") (class "Default")
      (node (ref "D1") (pin "A") (pinfunction "A_A") (pintype "passive"))
      (node (ref "R11") (pin "1") (pinfunction "1_1") (pintype "passive"))
    )
    (net (code "58") (name "Net-(D2-PadA)") (class "Default")
      (node (ref "D2") (pin "A") (pinfunction "A_A") (pintype "passive"))
      (node (ref "R12") (pin "1") (pinfunction "1_1") (pintype "passive"))
    )
    (net (code "59") (name "Net-(E2-Pad1)") (class "Default")
      (node (ref "E2") (pin "1") (pinfunction "1_1") (pintype "bidirectional"))
      (node (ref "R18") (pin "2") (pinfunction "2_2") (pintype "passive"))
      (node (ref "U7") (pin "5F") (pinfunction "ST1_5F") (pintype "input"))
      (node (ref "U7") (pin "5G") (pinfunction "ST1_5G") (pintype "input"))
    )
    (net (code "60") (name "Net-(E3-Pad1)") (class "Default")
      (node (ref "E3") (pin "1") (pinfunction "1_1") (pintype "bidirectional"))
      (node (ref "R19") (pin "2") (pinfunction "2_2") (pintype "passive"))
      (node (ref "U7") (pin "4F") (pinfunction "ST2_4F") (pintype "input"))
      (node (ref "U7") (pin "4G") (pinfunction "ST2_4G") (pintype "input"))
    )
    (net (code "61") (name "Net-(P3B-1)") (class "Default")
      (node (ref "C94") (pin "1") (pinfunction "1_1") (pintype "passive"))
      (node (ref "P3") (pin "10") (pinfunction "1_10") (pintype "bidirectional"))
      (node (ref "R43") (pin "1") (pinfunction "1_1") (pintype "passive"))
      (node (ref "U14") (pin "5") (pinfunction "IN+_5") (pintype "input"))
    )
    (net (code "62") (name "Net-(P3G-1)") (class "Default")
      (node (ref "P3") (pin "4") (pinfunction "1_4") (pintype "bidirectional"))
      (node (ref "R53") (pin "2") (pinfunction "2_2") (pintype "passive"))
    )
    (net (code "63") (name "Net-(P3H-1)") (class "Default")
      (node (ref "P3") (pin "5") (pinfunction "1_5") (pintype "bidirectional"))
      (node (ref "R57") (pin "2") (pinfunction "2_2") (pintype "passive"))
    )
    (net (code "64") (name "Net-(P3I-1)") (class "Default")
      (node (ref "C102") (pin "1") (pinfunction "1_1") (pintype "passive"))
      (node (ref "P3") (pin "6") (pinfunction "1_6") (pintype "bidirectional"))
      (node (ref "U16") (pin "3") (pinfunction "IN+_3") (pintype "input"))
    )
    (net (code "65") (name "Net-(P3J-1)") (class "Default")
      (node (ref "P3") (pin "7") (pinfunction "1_7") (pintype "bidirectional"))
      (node (ref "R45") (pin "2") (pinfunction "2_2") (pintype "passive"))
    )
    (net (code "66") (name "Net-(P3K-1)") (class "Default")
      (node (ref "P3") (pin "8") (pinfunction "1_8") (pintype "bidirectional"))
      (node (ref "R39") (pin "1") (pinfunction "1_1") (pintype "passive"))
    )
    (net (code "67") (name "Net-(P3L-1)") (class "Default")
      (node (ref "P3") (pin "9") (pinfunction "1_9") (pintype "bidirectional"))
      (node (ref "R31") (pin "1") (pinfunction "1_1") (pintype "passive"))
    )
    (net (code "68") (name "Net-(P4B-1)") (class "Default")
      (node (ref "C95") (pin "1") (pinfunction "1_1") (pintype "passive"))
      (node (ref "P4") (pin "10") (pinfunction "1_10") (pintype "bidirectional"))
      (node (ref "R44") (pin "1") (pinfunction "1_1") (pintype "passive"))
      (node (ref "U10") (pin "10") (pinfunction "IN+_10") (pintype "input"))
    )
    (net (code "69") (name "Net-(P4G-1)") (class "Default")
      (node (ref "P4") (pin "4") (pinfunction "1_4") (pintype "bidirectional"))
      (node (ref "R55") (pin "2") (pinfunction "2_2") (pintype "passive"))
    )
    (net (code "70") (name "Net-(P4H-1)") (class "Default")
      (node (ref "E5") (pin "1") (pinfunction "1_1") (pintype "bidirectional"))
      (node (ref "P4") (pin "5") (pinfunction "1_5") (pintype "bidirectional"))
    )
    (net (code "71") (name "Net-(P4I-1)") (class "Default")
      (node (ref "C103") (pin "1") (pinfunction "1_1") (pintype "passive"))
      (node (ref "P4") (pin "6") (pinfunction "1_6") (pintype "bidirectional"))
      (node (ref "U15") (pin "10") (pinfunction "IN+_10") (pintype "input"))
    )
    (net (code "72") (name "Net-(P4J-1)") (class "Default")
      (node (ref "P4") (pin "7") (pinfunction "1_7") (pintype "bidirectional"))
      (node (ref "R46") (pin "2") (pinfunction "2_2") (pintype "passive"))
    )
    (net (code "73") (name "Net-(P4K-1)") (class "Default")
      (node (ref "P4") (pin "8") (pinfunction "1_8") (pintype "bidirectional"))
      (node (ref "R40") (pin "1") (pinfunction "1_1") (pintype "passive"))
    )
    (net (code "74") (name "Net-(P4L-1)") (class "Default")
      (node (ref "P4") (pin "9") (pinfunction "1_9") (pintype "bidirectional"))
      (node (ref "R32") (pin "1") (pinfunction "1_1") (pintype "passive"))
    )
    (net (code "75") (name "Net-(R23-Pad1)") (class "Default")
      (node (ref "R23") (pin "1") (pinfunction "1_1") (pintype "passive"))
      (node (ref "U9") (pin "8") (pinfunction "RG_8") (pintype "input"))
    )
    (net (code "76") (name "Net-(R23-Pad2)") (class "Default")
      (node (ref "R23") (pin "2") (pinfunction "2_2") (pintype "passive"))
      (node (ref "U9") (pin "1") (pinfunction "RG_1") (pintype "input"))
    )
    (net (code "77") (name "Net-(R33-Pad1)") (class "Default")
      (node (ref "R33") (pin "1") (pinfunction "1_1") (pintype "passive"))
      (node (ref "U12") (pin "8") (pinfunction "RG_8") (pintype "input"))
    )
    (net (code "78") (name "Net-(R33-Pad2)") (class "Default")
      (node (ref "R33") (pin "2") (pinfunction "2_2") (pintype "passive"))
      (node (ref "U12") (pin "1") (pinfunction "RG_1") (pintype "input"))
    )
    (net (code "79") (name "Net-(R36-Pad1)") (class "Default")
      (node (ref "R36") (pin "1") (pinfunction "1_1") (pintype "passive"))
      (node (ref "U13") (pin "8") (pinfunction "RG_8") (pintype "input"))
    )
    (net (code "80") (name "Net-(R36-Pad2)") (class "Default")
      (node (ref "R36") (pin "2") (pinfunction "2_2") (pintype "passive"))
      (node (ref "U13") (pin "1") (pinfunction "RG_1") (pintype "input"))
    )
    (net (code "81") (name "Net-(REG1-BYP)") (class "Default")
      (node (ref "C117") (pin "2") (pinfunction "2_2") (pintype "passive"))
      (node (ref "REG1") (pin "3") (pinfunction "BYP_3") (pintype "input"))
    )
    (net (code "82") (name "Net-(REG1-SENSE{slash}ADJ)") (class "Default")
      (node (ref "C117") (pin "1") (pinfunction "1_1") (pintype "passive"))
      (node (ref "R67") (pin "2") (pinfunction "2_2") (pintype "passive"))
      (node (ref "R68") (pin "1") (pinfunction "1_1") (pintype "passive"))
      (node (ref "REG1") (pin "2") (pinfunction "SENSE/ADJ_2") (pintype "input"))
    )
    (net (code "83") (name "Net-(REG2-BYP)") (class "Default")
      (node (ref "C122") (pin "2") (pinfunction "2_2") (pintype "passive"))
      (node (ref "REG2") (pin "3") (pinfunction "BYP_3") (pintype "input"))
    )
    (net (code "84") (name "Net-(REG3-BYP)") (class "Default")
      (node (ref "C127") (pin "2") (pinfunction "2_2") (pintype "passive"))
      (node (ref "REG3") (pin "3") (pinfunction "BYP_3") (pintype "input"))
    )
    (net (code "85") (name "Net-(REG4-BYP)") (class "Default")
      (node (ref "C131") (pin "2") (pinfunction "2_2") (pintype "passive"))
      (node (ref "REG4") (pin "3") (pinfunction "BYP_3") (pintype "input"))
    )
    (net (code "86") (name "Net-(REG4-SENSE{slash}ADJ)") (class "Default")
      (node (ref "C131") (pin "1") (pinfunction "1_1") (pintype "passive"))
      (node (ref "R69") (pin "2") (pinfunction "2_2") (pintype "passive"))
      (node (ref "R70") (pin "1") (pinfunction "1_1") (pintype "passive"))
      (node (ref "REG4") (pin "2") (pinfunction "SENSE/ADJ_2") (pintype "input"))
    )
    (net (code "87") (name "Net-(U1-~{RESET})") (class "Default")
      (node (ref "C31") (pin "1") (pinfunction "1_1") (pintype "passive"))
      (node (ref "R4") (pin "2") (pinfunction "2_2") (pintype "passive"))
      (node (ref "U1") (pin "1") (pinfunction "~{RESET}_1") (pintype "bidirectional"))
      (node (ref "U3") (pin "M13") (pinfunction "~{XRS}_M13") (pintype "bidirectional"))
    )
    (net (code "88") (name "Net-(U3-ADCINA0)") (class "Default")
      (node (ref "C42") (pin "1") (pinfunction "1_1") (pintype "passive"))
      (node (ref "RN1") (pin "1") (pinfunction "1_1") (pintype "passive"))
      (node (ref "U3") (pin "M3") (pinfunction "ADCINA0_M3") (pintype "bidirectional"))
    )
    (net (code "89") (name "Net-(U3-ADCINA1)") (class "Default")
      (node (ref "C41") (pin "1") (pinfunction "1_1") (pintype "passive"))
      (node (ref "RN1") (pin "2") (pinfunction "2_2") (pintype "passive"))
      (node (ref "U3") (pin "M2") (pinfunction "ADCINA1_M2") (pintype "bidirectional"))
    )
    (net (code "90") (name "Net-(U3-ADCINA2)") (class "Default")
      (node (ref "C40") (pin "1") (pinfunction "1_1") (pintype "passive"))
      (node (ref "RN1") (pin "3") (pinfunction "3_3") (pintype "passive"))
      (node (ref "U3") (pin "M1") (pinfunction "ADCINA2_M1") (pintype "bidirectional"))
    )
    (net (code "91") (name "Net-(U3-ADCINA3)") (class "Default")
      (node (ref "C39") (pin "1") (pinfunction "1_1") (pintype "passive"))
      (node (ref "RN1") (pin "4") (pinfunction "4_4") (pintype "passive"))
      (node (ref "U3") (pin "L3") (pinfunction "ADCINA3_L3") (pintype "bidirectional"))
    )
    (net (code "92") (name "Net-(U3-ADCINA4)") (class "Default")
      (node (ref "C38") (pin "1") (pinfunction "1_1") (pintype "passive"))
      (node (ref "RN1") (pin "5") (pinfunction "5_5") (pintype "passive"))
      (node (ref "U3") (pin "L2") (pinfunction "ADCINA4_L2") (pintype "bidirectional"))
    )
    (net (code "93") (name "Net-(U3-ADCINA5)") (class "Default")
      (node (ref "C37") (pin "1") (pinfunction "1_1") (pintype "passive"))
      (node (ref "RN1") (pin "6") (pinfunction "6_6") (pintype "passive"))
      (node (ref "U3") (pin "L1") (pinfunction "ADCINA5_L1") (pintype "bidirectional"))
    )
    (net (code "94") (name "Net-(U3-ADCINA6)") (class "Default")
      (node (ref "C36") (pin "1") (pinfunction "1_1") (pintype "passive"))
      (node (ref "RN1") (pin "7") (pinfunction "7_7") (pintype "passive"))
      (node (ref "U3") (pin "K2") (pinfunction "ADCINA6_K2") (pintype "bidirectional"))
    )
    (net (code "95") (name "Net-(U3-ADCINA7)") (class "Default")
      (node (ref "C35") (pin "1") (pinfunction "1_1") (pintype "passive"))
      (node (ref "RN1") (pin "8") (pinfunction "8_8") (pintype "passive"))
      (node (ref "U3") (pin "K1") (pinfunction "ADCINA7_K1") (pintype "bidirectional"))
    )
    (net (code "96") (name "Net-(U3-ADCINB0)") (class "Default")
      (node (ref "C45") (pin "1") (pinfunction "1_1") (pintype "passive"))
      (node (ref "RN2") (pin "16") (pinfunction "16_16") (pintype "passive"))
      (node (ref "U3") (pin "P3") (pinfunction "ADCINB0_P3") (pintype "bidirectional"))
    )
    (net (code "97") (name "Net-(U3-ADCINB1)") (class "Default")
      (node (ref "C46") (pin "1") (pinfunction "1_1") (pintype "passive"))
      (node (ref "RN2") (pin "15") (pinfunction "15_15") (pintype "passive"))
      (node (ref "U3") (pin "N3") (pinfunction "ADCINB1_N3") (pintype "bidirectional"))
    )
    (net (code "98") (name "Net-(U3-ADCINB2)") (class "Default")
      (node (ref "C47") (pin "1") (pinfunction "1_1") (pintype "passive"))
      (node (ref "RN2") (pin "14") (pinfunction "14_14") (pintype "passive"))
      (node (ref "U3") (pin "M4") (pinfunction "ADCINB2_M4") (pintype "bidirectional"))
    )
    (net (code "99") (name "Net-(U3-ADCINB3)") (class "Default")
      (node (ref "C48") (pin "1") (pinfunction "1_1") (pintype "passive"))
      (node (ref "RN2") (pin "13") (pinfunction "13_13") (pintype "passive"))
      (node (ref "U3") (pin "N4") (pinfunction "ADCINB3_N4") (pintype "bidirectional"))
    )
    (net (code "100") (name "Net-(U3-ADCINB4)") (class "Default")
      (node (ref "C49") (pin "1") (pinfunction "1_1") (pintype "passive"))
      (node (ref "RN2") (pin "12") (pinfunction "12_12") (pintype "passive"))
      (node (ref "U3") (pin "M5") (pinfunction "ADCINB4_M5") (pintype "bidirectional"))
    )
    (net (code "101") (name "Net-(U3-ADCINB5)") (class "Default")
      (node (ref "C50") (pin "1") (pinfunction "1_1") (pintype "passive"))
      (node (ref "RN2") (pin "11") (pinfunction "11_11") (pintype "passive"))
      (node (ref "U3") (pin "N5") (pinfunction "ADCINB5_N5") (pintype "bidirectional"))
    )
    (net (code "102") (name "Net-(U3-ADCINB6)") (class "Default")
      (node (ref "C51") (pin "1") (pinfunction "1_1") (pintype "passive"))
      (node (ref "RN2") (pin "10") (pinfunction "10_10") (pintype "passive"))
      (node (ref "U3") (pin "M6") (pinfunction "ADCINB6_M6") (pintype "bidirectional"))
    )
    (net (code "103") (name "Net-(U3-ADCINB7)") (class "Default")
      (node (ref "C52") (pin "1") (pinfunction "1_1") (pintype "passive"))
      (node (ref "RN2") (pin "9") (pinfunction "9_9") (pintype "passive"))
      (node (ref "U3") (pin "N6") (pinfunction "ADCINB7_N6") (pintype "bidirectional"))
    )
    (net (code "104") (name "Net-(U3-ADCREFM)") (class "Default")
      (node (ref "C54") (pin "1") (pinfunction "1_1") (pintype "passive"))
      (node (ref "U3") (pin "P4") (pinfunction "ADCREFM_P4") (pintype "bidirectional"))
    )
    (net (code "105") (name "Net-(U3-ADCREFP)") (class "Default")
      (node (ref "C53") (pin "1") (pinfunction "1_1") (pintype "passive"))
      (node (ref "U3") (pin "P5") (pinfunction "ADCREFP_P5") (pintype "bidirectional"))
    )
    (net (code "106") (name "Net-(U3-ADCRESEXT)") (class "Default")
      (node (ref "R7") (pin "2") (pinfunction "2_2") (pintype "passive"))
      (node (ref "U3") (pin "P6") (pinfunction "ADCRESEXT_P6") (pintype "bidirectional"))
    )
    (net (code "107") (name "Net-(U3-GPIO54{slash}XD25{slash}SPISIMOA)") (class "Default")
      (node (ref "U3") (pin "J14") (pinfunction "GPIO54/XD25/SPISIMOA_J14") (pintype "bidirectional"))
      (node (ref "U4") (pin "3") (pinfunction "SDI_3") (pintype "input"))
    )
    (net (code "108") (name "Net-(U3-GPIO55{slash}XD24{slash}SPISOMIA)") (class "Default")
      (node (ref "U3") (pin "J13") (pinfunction "GPIO55/XD24/SPISOMIA_J13") (pintype "bidirectional"))
      (node (ref "U4") (pin "2") (pinfunction "SDO_2") (pintype "output"))
    )
    (net (code "109") (name "Net-(U3-GPIO56{slash}XD23{slash}SPICLKA)") (class "Default")
      (node (ref "U3") (pin "J12") (pinfunction "GPIO56/XD23/SPICLKA_J12") (pintype "bidirectional"))
      (node (ref "U4") (pin "5") (pinfunction "SPC_5") (pintype "input"))
    )
    (net (code "110") (name "Net-(U3-X1)") (class "Default")
      (node (ref "C34") (pin "1") (pinfunction "1_1") (pintype "passive"))
      (node (ref "U3") (pin "G14") (pinfunction "X1_G14") (pintype "bidirectional"))
      (node (ref "X1") (pin "2") (pinfunction "2_2") (pintype "passive"))
    )
    (net (code "111") (name "Net-(U3-X2)") (class "Default")
      (node (ref "C33") (pin "1") (pinfunction "1_1") (pintype "passive"))
      (node (ref "U3") (pin "H14") (pinfunction "X2_H14") (pintype "bidirectional"))
      (node (ref "X1") (pin "1") (pinfunction "1_1") (pintype "passive"))
    )
    (net (code "112") (name "Net-(U6-1Y)") (class "Default")
      (node (ref "D1") (pin "C") (pinfunction "C_C") (pintype "passive"))
      (node (ref "U6") (pin "6") (pinfunction "1Y_6") (pintype "bidirectional"))
    )
    (net (code "113") (name "Net-(U6-2Y)") (class "Default")
      (node (ref "D2") (pin "C") (pinfunction "C_C") (pintype "passive"))
      (node (ref "U6") (pin "4") (pinfunction "2Y_4") (pintype "bidirectional"))
    )
    (net (code "114") (name "Net-(U8A-IN+)") (class "Default")
      (node (ref "R13") (pin "1") (pinfunction "1_1") (pintype "passive"))
      (node (ref "R17") (pin "1") (pinfunction "1_1") (pintype "passive"))
      (node (ref "U8") (pin "3") (pinfunction "IN+_3") (pintype "input"))
    )
    (net (code "115") (name "Net-(U8A-IN-)") (class "Default")
      (node (ref "R14") (pin "2") (pinfunction "2_2") (pintype "passive"))
      (node (ref "U8") (pin "1") (pinfunction "OUT_1") (pintype "output"))
      (node (ref "U8") (pin "2") (pinfunction "IN-_2") (pintype "input"))
    )
    (net (code "116") (name "Net-(U8B-IN+)") (class "Default")
      (node (ref "C63") (pin "1") (pinfunction "1_1") (pintype "passive"))
      (node (ref "R15") (pin "1") (pinfunction "1_1") (pintype "passive"))
      (node (ref "U8") (pin "5") (pinfunction "IN+_5") (pintype "input"))
    )
    (net (code "117") (name "Net-(U8C-IN+)") (class "Default")
      (node (ref "C66") (pin "1") (pinfunction "1_1") (pintype "passive"))
      (node (ref "U7") (pin "3F") (pinfunction "TEMP_3F") (pintype "output"))
      (node (ref "U7") (pin "3G") (pinfunction "TEMP_3G") (pintype "output"))
      (node (ref "U8") (pin "10") (pinfunction "IN+_10") (pintype "input"))
    )
    (net (code "118") (name "Net-(U8D-IN+)") (class "Default")
      (node (ref "C67") (pin "1") (pinfunction "1_1") (pintype "passive"))
      (node (ref "R20") (pin "2") (pinfunction "2_2") (pintype "passive"))
      (node (ref "R21") (pin "2") (pinfunction "2_2") (pintype "passive"))
      (node (ref "U8") (pin "12") (pinfunction "IN+_12") (pintype "input"))
    )
    (net (code "119") (name "Net-(U9-IN+)") (class "Default")
      (node (ref "C69") (pin "2") (pinfunction "2_2") (pintype "passive"))
      (node (ref "C72") (pin "1") (pinfunction "1_1") (pintype "passive"))
      (node (ref "R22") (pin "2") (pinfunction "2_2") (pintype "passive"))
      (node (ref "U9") (pin "3") (pinfunction "IN+_3") (pintype "input"))
    )
    (net (code "120") (name "Net-(U9-IN-)") (class "Default")
      (node (ref "C72") (pin "2") (pinfunction "2_2") (pintype "passive"))
      (node (ref "C76") (pin "1") (pinfunction "1_1") (pintype "passive"))
      (node (ref "R26") (pin "2") (pinfunction "2_2") (pintype "passive"))
      (node (ref "U9") (pin "2") (pinfunction "IN-_2") (pintype "input"))
    )
    (net (code "121") (name "Net-(U9-VOUT)") (class "Default")
      (node (ref "R24") (pin "1") (pinfunction "1_1") (pintype "passive"))
      (node (ref "U9") (pin "6") (pinfunction "VOUT_6") (pintype "output"))
    )
    (net (code "122") (name "Net-(U10A-IN+)") (class "Default")
      (node (ref "C75") (pin "1") (pinfunction "1_1") (pintype "passive"))
      (node (ref "R25") (pin "1") (pinfunction "1_1") (pintype "passive"))
      (node (ref "U10") (pin "3") (pinfunction "IN+_3") (pintype "input"))
    )
    (net (code "123") (name "Net-(U10B-IN+)") (class "Default")
      (node (ref "C78") (pin "1") (pinfunction "1_1") (pintype "passive"))
      (node (ref "R30") (pin "1") (pinfunction "1_1") (pintype "passive"))
      (node (ref "U10") (pin "5") (pinfunction "IN+_5") (pintype "input"))
      (node (ref "U11") (pin "8") (pinfunction "IT_8") (pintype "output"))
    )
    (net (code "124") (name "Net-(U10D-IN+)") (class "Default")
      (node (ref "C91") (pin "1") (pinfunction "1_1") (pintype "passive"))
      (node (ref "R38") (pin "1") (pinfunction "1_1") (pintype "passive"))
      (node (ref "U10") (pin "12") (pinfunction "IN+_12") (pintype "input"))
    )
    (net (code "125") (name "Net-(U11-2.5V)") (class "Default")
      (node (ref "C77") (pin "1") (pinfunction "1_1") (pintype "passive"))
      (node (ref "R28") (pin "1") (pinfunction "1_1") (pintype "passive"))
      (node (ref "R29") (pin "2") (pinfunction "2_2") (pintype "passive"))
      (node (ref "U11") (pin "17") (pinfunction "2.5V_17") (pintype "bidirectional"))
    )
    (net (code "126") (name "Net-(U11-AON)") (class "Default")
      (node (ref "R26") (pin "1") (pinfunction "1_1") (pintype "passive"))
      (node (ref "U11") (pin "16") (pinfunction "AON_16") (pintype "output"))
    )
    (net (code "127") (name "Net-(U11-AOP)") (class "Default")
      (node (ref "R22") (pin "1") (pinfunction "1_1") (pintype "passive"))
      (node (ref "U11") (pin "12") (pinfunction "AOP_12") (pintype "output"))
    )
    (net (code "128") (name "Net-(U11-DV)") (class "Default")
      (node (ref "E4") (pin "1") (pinfunction "1_1") (pintype "bidirectional"))
      (node (ref "U11") (pin "4") (pinfunction "DV_4") (pintype "input"))
    )
    (net (code "129") (name "Net-(U12-IN+)") (class "Default")
      (node (ref "C81") (pin "2") (pinfunction "2_2") (pintype "passive"))
      (node (ref "C86") (pin "1") (pinfunction "1_1") (pintype "passive"))
      (node (ref "R31") (pin "2") (pinfunction "2_2") (pintype "passive"))
      (node (ref "U12") (pin "3") (pinfunction "IN+_3") (pintype "input"))
    )
    (net (code "130") (name "Net-(U12-IN-)") (class "Default")
      (node (ref "C86") (pin "2") (pinfunction "2_2") (pintype "passive"))
      (node (ref "C92") (pin "1") (pinfunction "1_1") (pintype "passive"))
      (node (ref "R39") (pin "2") (pinfunction "2_2") (pintype "passive"))
      (node (ref "U12") (pin "2") (pinfunction "IN-_2") (pintype "input"))
    )
    (net (code "131") (name "Net-(U12-VOUT)") (class "Default")
      (node (ref "R34") (pin "1") (pinfunction "1_1") (pintype "passive"))
      (node (ref "U12") (pin "6") (pinfunction "VOUT_6") (pintype "output"))
    )
    (net (code "132") (name "Net-(U13-IN+)") (class "Default")
      (node (ref "C82") (pin "2") (pinfunction "2_2") (pintype "passive"))
      (node (ref "C87") (pin "1") (pinfunction "1_1") (pintype "passive"))
      (node (ref "R32") (pin "2") (pinfunction "2_2") (pintype "passive"))
      (node (ref "U13") (pin "3") (pinfunction "IN+_3") (pintype "input"))
    )
    (net (code "133") (name "Net-(U13-IN-)") (class "Default")
      (node (ref "C87") (pin "2") (pinfunction "2_2") (pintype "passive"))
      (node (ref "C93") (pin "1") (pinfunction "1_1") (pintype "passive"))
      (node (ref "R40") (pin "2") (pinfunction "2_2") (pintype "passive"))
      (node (ref "U13") (pin "2") (pinfunction "IN-_2") (pintype "input"))
    )
    (net (code "134") (name "Net-(U13-VOUT)") (class "Default")
      (node (ref "R37") (pin "1") (pinfunction "1_1") (pintype "passive"))
      (node (ref "U13") (pin "6") (pinfunction "VOUT_6") (pintype "output"))
    )
    (net (code "135") (name "Net-(U14A-IN+)") (class "Default")
      (node (ref "C89") (pin "1") (pinfunction "1_1") (pintype "passive"))
      (node (ref "R35") (pin "1") (pinfunction "1_1") (pintype "passive"))
      (node (ref "U14") (pin "3") (pinfunction "IN+_3") (pintype "input"))
    )
    (net (code "136") (name "Net-(U14C-IN+)") (class "Default")
      (node (ref "R45") (pin "1") (pinfunction "1_1") (pintype "passive"))
      (node (ref "R51") (pin "1") (pinfunction "1_1") (pintype "passive"))
      (node (ref "U14") (pin "10") (pinfunction "IN+_10") (pintype "input"))
    )
    (net (code "137") (name "Net-(U14C-IN-)") (class "Default")
      (node (ref "R47") (pin "2") (pinfunction "2_2") (pintype "passive"))
      (node (ref "U14") (pin "8") (pinfunction "OUT_8") (pintype "output"))
      (node (ref "U14") (pin "9") (pinfunction "IN-_9") (pintype "input"))
    )
    (net (code "138") (name "Net-(U14D-IN+)") (class "Default")
      (node (ref "C98") (pin "1") (pinfunction "1_1") (pintype "passive"))
      (node (ref "R48") (pin "1") (pinfunction "1_1") (pintype "passive"))
      (node (ref "U14") (pin "12") (pinfunction "IN+_12") (pintype "input"))
    )
    (net (code "139") (name "Net-(U15A-IN+)") (class "Default")
      (node (ref "R46") (pin "1") (pinfunction "1_1") (pintype "passive"))
      (node (ref "R52") (pin "1") (pinfunction "1_1") (pintype "passive"))
      (node (ref "U15") (pin "3") (pinfunction "IN+_3") (pintype "input"))
    )
    (net (code "140") (name "Net-(U15A-IN-)") (class "Default")
      (node (ref "R49") (pin "2") (pinfunction "2_2") (pintype "passive"))
      (node (ref "U15") (pin "1") (pinfunction "OUT_1") (pintype "output"))
      (node (ref "U15") (pin "2") (pinfunction "IN-_2") (pintype "input"))
    )
    (net (code "141") (name "Net-(U15B-IN+)") (class "Default")
      (node (ref "C100") (pin "1") (pinfunction "1_1") (pintype "passive"))
      (node (ref "R50") (pin "1") (pinfunction "1_1") (pintype "passive"))
      (node (ref "U15") (pin "5") (pinfunction "IN+_5") (pintype "input"))
    )
    (net (code "142") (name "Net-(U15D-IN+)") (class "Default")
      (node (ref "C107") (pin "1") (pinfunction "1_1") (pintype "passive"))
      (node (ref "R56") (pin "1") (pinfunction "1_1") (pintype "passive"))
      (node (ref "U15") (pin "12") (pinfunction "IN+_12") (pintype "input"))
    )
    (net (code "143") (name "Net-(U16B-IN+)") (class "Default")
      (node (ref "C105") (pin "1") (pinfunction "1_1") (pintype "passive"))
      (node (ref "R54") (pin "1") (pinfunction "1_1") (pintype "passive"))
      (node (ref "U16") (pin "5") (pinfunction "IN+_5") (pintype "input"))
    )
    (net (code "144") (name "Net-(U16C-IN+)") (class "Default")
      (node (ref "C109") (pin "1") (pinfunction "1_1") (pintype "passive"))
      (node (ref "R58") (pin "1") (pinfunction "1_1") (pintype "passive"))
      (node (ref "U16") (pin "10") (pinfunction "IN+_10") (pintype "input"))
    )
    (net (code "145") (name "Net-(U16D-IN+)") (class "Default")
      (node (ref "E6") (pin "1") (pinfunction "1_1") (pintype "bidirectional"))
      (node (ref "R59") (pin "1") (pinfunction "1_1") (pintype "passive"))
      (node (ref "U16") (pin "12") (pinfunction "IN+_12") (pintype "input"))
    )
    (net (code "146") (name "Net-(U16D-IN-)") (class "Default")
      (node (ref "E7") (pin "1") (pinfunction "1_1") (pintype "bidirectional"))
      (node (ref "U16") (pin "13") (pinfunction "IN-_13") (pintype "input"))
      (node (ref "U16") (pin "14") (pinfunction "OUT_14") (pintype "output"))
    )
    (net (code "147") (name "Net-(U17-ADJ2)") (class "Default")
      (node (ref "C114") (pin "2") (pinfunction "2_2") (pintype "passive"))
      (node (ref "R65") (pin "1") (pinfunction "1_1") (pintype "passive"))
      (node (ref "R66") (pin "2") (pinfunction "2_2") (pintype "passive"))
      (node (ref "U17") (pin "1") (pinfunction "ADJ2_1") (pintype "input"))
    )
    (net (code "148") (name "Net-(U17-DEF_1)") (class "Default")
      (node (ref "R60") (pin "2") (pinfunction "2_2") (pintype "passive"))
      (node (ref "R63") (pin "1") (pinfunction "1_1") (pintype "passive"))
      (node (ref "U17") (pin "5") (pinfunction "DEF_1_5") (pintype "input"))
    )
    (net (code "149") (name "Net-(U17-EN_1)") (class "Default")
      (node (ref "C113") (pin "1") (pinfunction "1_1") (pintype "passive"))
      (node (ref "R61") (pin "2") (pinfunction "2_2") (pintype "passive"))
      (node (ref "U17") (pin "7") (pinfunction "EN_1_7") (pintype "input"))
    )
    (net (code "150") (name "Net-(U17-MODE)") (class "Default")
      (node (ref "R62") (pin "2") (pinfunction "2_2") (pintype "passive"))
      (node (ref "R64") (pin "1") (pinfunction "1_1") (pintype "passive"))
      (node (ref "U17") (pin "2") (pinfunction "MODE_2") (pintype "bidirectional"))
    )
    (net (code "151") (name "Net-(U17-SW1)") (class "Default")
      (node (ref "L1") (pin "1") (pinfunction "1_1") (pintype "passive"))
      (node (ref "U17") (pin "6") (pinfunction "SW1_6") (pintype "bidirectional"))
    )
    (net (code "152") (name "Net-(U17-SW2)") (class "Default")
      (node (ref "L2") (pin "1") (pinfunction "1_1") (pintype "passive"))
      (node (ref "U17") (pin "10") (pinfunction "SW2_10") (pintype "bidirectional"))
    )
    (net (code "153") (name "Net-(U18-RS)") (class "Default")
      (node (ref "R71") (pin "2") (pinfunction "2_2") (pintype "passive"))
      (node (ref "U18") (pin "8") (pinfunction "RS_8") (pintype "input"))
    )
    (net (code "154") (name "REF_MON") (class "Default")
      (node (ref "RN1") (pin "15") (pinfunction "15_15") (pintype "passive"))
      (node (ref "U8") (pin "13") (pinfunction "IN-_13") (pintype "input"))
      (node (ref "U8") (pin "14") (pinfunction "OUT_14") (pintype "output"))
    )
    (net (code "155") (name "SER_DE") (class "Default")
      (node (ref "U2") (pin "4") (pinfunction "DE_4") (pintype "input"))
      (node (ref "U3") (pin "M10") (pinfunction "GPIO25/ECAP2/EQEP2B/MDRB_M10") (pintype "bidirectional"))
    )
    (net (code "156") (name "SER_DI") (class "Default")
      (node (ref "U2") (pin "5") (pinfunction "DI_5") (pintype "input"))
      (node (ref "U3") (pin "M9") (pinfunction "GPIO22/EQEP1S/MCLKXA/SCITXDB_M9") (pintype "bidirectional"))
    )
    (net (code "157") (name "SER_H{slash}~{F}") (class "Default")
      (node (ref "U2") (pin "1") (pinfunction "H/~{F}_1") (pintype "input"))
      (node (ref "U3") (pin "P11") (pinfunction "GPIO26/ECAP3/EQEP2I/MCLKXB_P11") (pintype "bidirectional"))
    )
    (net (code "158") (name "SER_RO") (class "Default")
      (node (ref "U2") (pin "2") (pinfunction "RO_2") (pintype "output"))
      (node (ref "U3") (pin "P10") (pinfunction "GPIO23/EQEP1I/MFSXA/SCIRXDB_P10") (pintype "bidirectional"))
    )
    (net (code "159") (name "SER_~{RE}") (class "Default")
      (node (ref "U2") (pin "3") (pinfunction "~{RE}_3") (pintype "input"))
      (node (ref "U3") (pin "N10") (pinfunction "GPIO24/ECAP1/EQEP2A/MDXB_N10") (pintype "bidirectional"))
    )
    (net (code "160") (name "SPARE0") (class "Default")
      (node (ref "P1") (pin "14") (pinfunction "1_14") (pintype "bidirectional"))
      (node (ref "U3") (pin "A9") (pinfunction "GPIO34/ECAP1/XREADY_A9") (pintype "bidirectional"))
    )
    (net (code "161") (name "SPARE1") (class "Default")
      (node (ref "P1") (pin "13") (pinfunction "1_13") (pintype "bidirectional"))
      (node (ref "U3") (pin "A7") (pinfunction "GPIO41/XA1_A7") (pintype "bidirectional"))
    )
    (net (code "162") (name "SPARE2") (class "Default")
      (node (ref "P1") (pin "12") (pinfunction "1_12") (pintype "bidirectional"))
      (node (ref "U3") (pin "A6") (pinfunction "GPIO44/XA4_A6") (pintype "bidirectional"))
    )
    (net (code "163") (name "SPARE_MCLKX") (class "Default")
      (node (ref "P1") (pin "11") (pinfunction "1_11") (pintype "bidirectional"))
      (node (ref "U3") (pin "H3") (pinfunction "GPIO14/~{TZ3}/~{XHOLD}/SCITXDB/MCLKXB_H3") (pintype "bidirectional"))
    )
    (net (code "164") (name "SPARE_MDR") (class "Default")
      (node (ref "P1") (pin "9") (pinfunction "1_9") (pintype "bidirectional"))
      (node (ref "U3") (pin "H2") (pinfunction "GPIO13/~{TZ2}/CANRXB/MDRB_H2") (pintype "bidirectional"))
    )
    (net (code "165") (name "SPARE_MDX") (class "Default")
      (node (ref "P1") (pin "10") (pinfunction "1_10") (pintype "bidirectional"))
      (node (ref "U3") (pin "H1") (pinfunction "GPIO12/~{TZ1}/CANTXB/MDXB_H1") (pintype "bidirectional"))
    )
    (net (code "166") (name "TCK") (class "Default")
      (node (ref "S1") (pin "3") (pinfunction "1_3") (pintype "bidirectional"))
      (node (ref "U3") (pin "M14") (pinfunction "TCK_M14") (pintype "bidirectional"))
    )
    (net (code "167") (name "TDI") (class "Default")
      (node (ref "S1") (pin "5") (pinfunction "1_5") (pintype "bidirectional"))
      (node (ref "U3") (pin "N12") (pinfunction "TDI_N12") (pintype "bidirectional"))
    )
    (net (code "168") (name "TDO") (class "Default")
      (node (ref "S1") (pin "6") (pinfunction "1_6") (pintype "bidirectional"))
      (node (ref "U3") (pin "N13") (pinfunction "TDO_N13") (pintype "bidirectional"))
    )
    (net (code "169") (name "TMS") (class "Default")
      (node (ref "S1") (pin "4") (pinfunction "1_4") (pintype "bidirectional"))
      (node (ref "U3") (pin "M12") (pinfunction "TMS_M12") (pintype "bidirectional"))
    )
    (net (code "170") (name "unconnected-(U1-WDI-Pad4)") (class "Default")
      (node (ref "U1") (pin "4") (pinfunction "WDI_4") (pintype "bidirectional"))
    )
    (net (code "171") (name "unconnected-(U1-~{MR}-Pad3)") (class "Default")
      (node (ref "U1") (pin "3") (pinfunction "~{MR}_3") (pintype "bidirectional"))
    )
    (net (code "172") (name "unconnected-(U3-GPIO1{slash}EPWM1B{slash}ECAP6{slash}MFSRB-PadD2)") (class "Default")
      (node (ref "U3") (pin "D2") (pinfunction "GPIO1/EPWM1B/ECAP6/MFSRB_D2") (pintype "bidirectional"))
    )
    (net (code "173") (name "unconnected-(U3-GPIO2{slash}EPWM2A-PadD3)") (class "Default")
      (node (ref "U3") (pin "D3") (pinfunction "GPIO2/EPWM2A_D3") (pintype "bidirectional"))
    )
    (net (code "174") (name "unconnected-(U3-GPIO3{slash}EPWM2B{slash}ECAP5{slash}MCLKRB-PadE1)") (class "Default")
      (node (ref "U3") (pin "E1") (pinfunction "GPIO3/EPWM2B/ECAP5/MCLKRB_E1") (pintype "bidirectional"))
    )
    (net (code "175") (name "unconnected-(U3-GPIO4{slash}EPWM3A-PadE2)") (class "Default")
      (node (ref "U3") (pin "E2") (pinfunction "GPIO4/EPWM3A_E2") (pintype "bidirectional"))
    )
    (net (code "176") (name "unconnected-(U3-GPIO5{slash}EPWM3B{slash}MFSRA{slash}ECAP1-PadE3)") (class "Default")
      (node (ref "U3") (pin "E3") (pinfunction "GPIO5/EPWM3B/MFSRA/ECAP1_E3") (pintype "bidirectional"))
    )
    (net (code "177") (name "unconnected-(U3-GPIO6{slash}EPWM4A{slash}EPWMSYNCI{slash}EPWMSYNCO-PadF1)") (class "Default")
      (node (ref "U3") (pin "F1") (pinfunction "GPIO6/EPWM4A/EPWMSYNCI/EPWMSYNCO_F1") (pintype "bidirectional"))
    )
    (net (code "178") (name "unconnected-(U3-GPIO7{slash}EPWM4B{slash}MCLKRA{slash}ECAP2-PadF2)") (class "Default")
      (node (ref "U3") (pin "F2") (pinfunction "GPIO7/EPWM4B/MCLKRA/ECAP2_F2") (pintype "bidirectional"))
    )
    (net (code "179") (name "unconnected-(U3-GPIO8{slash}EPWM5A{slash}CANTXB{slash}~{ADCSOCAO}-PadF3)") (class "Default")
      (node (ref "U3") (pin "F3") (pinfunction "GPIO8/EPWM5A/CANTXB/~{ADCSOCAO}_F3") (pintype "bidirectional"))
    )
    (net (code "180") (name "unconnected-(U3-GPIO10{slash}EPWM6A{slash}CANRXB{slash}~{ADCSOCBO}-PadG2)") (class "Default")
      (node (ref "U3") (pin "G2") (pinfunction "GPIO10/EPWM6A/CANRXB/~{ADCSOCBO}_G2") (pintype "bidirectional"))
    )
    (net (code "181") (name "unconnected-(U3-GPIO11{slash}EPWM6B{slash}SCIRXDB{slash}ECAP4-PadG3)") (class "Default")
      (node (ref "U3") (pin "G3") (pinfunction "GPIO11/EPWM6B/SCIRXDB/ECAP4_G3") (pintype "bidirectional"))
    )
    (net (code "182") (name "unconnected-(U3-GPIO15{slash}~{TZ4}{slash}~{XHOLDA}{slash}SCIRXDB{slash}MFSXB-PadJ1)") (class "Default")
      (node (ref "U3") (pin "J1") (pinfunction "GPIO15/~{TZ4}/~{XHOLDA}/SCIRXDB/MFSXB_J1") (pintype "bidirectional"))
    )
    (net (code "183") (name "unconnected-(U3-GPIO16{slash}SPISIMOA{slash}CANTXB{slash}~{TZ5}-PadJ2)") (class "Default")
      (node (ref "U3") (pin "J2") (pinfunction "GPIO16/SPISIMOA/CANTXB/~{TZ5}_J2") (pintype "bidirectional"))
    )
    (net (code "184") (name "unconnected-(U3-GPIO17{slash}SPISOMIA{slash}CANRXB{slash}~{TZ6}-PadJ3)") (class "Default")
      (node (ref "U3") (pin "J3") (pinfunction "GPIO17/SPISOMIA/CANRXB/~{TZ6}_J3") (pintype "bidirectional"))
    )
    (net (code "185") (name "unconnected-(U3-GPIO18{slash}SPICLKA{slash}SCITXDB{slash}CANRXA-PadN8)") (class "Default")
      (node (ref "U3") (pin "N8") (pinfunction "GPIO18/SPICLKA/SCITXDB/CANRXA_N8") (pintype "bidirectional"))
    )
    (net (code "186") (name "unconnected-(U3-GPIO19{slash}~{SPISTEA}{slash}SCIRXDB{slash}CANTXA-PadM8)") (class "Default")
      (node (ref "U3") (pin "M8") (pinfunction "GPIO19/~{SPISTEA}/SCIRXDB/CANTXA_M8") (pintype "bidirectional"))
    )
    (net (code "187") (name "unconnected-(U3-GPIO20{slash}EQEP1A{slash}MDXA{slash}CANTXB-PadP9)") (class "Default")
      (node (ref "U3") (pin "P9") (pinfunction "GPIO20/EQEP1A/MDXA/CANTXB_P9") (pintype "bidirectional"))
    )
    (net (code "188") (name "unconnected-(U3-GPIO21{slash}EQEP1B{slash}MDRA{slash}CANRXB-PadN9)") (class "Default")
      (node (ref "U3") (pin "N9") (pinfunction "GPIO21/EQEP1B/MDRA/CANRXB_N9") (pintype "bidirectional"))
    )
    (net (code "189") (name "unconnected-(U3-GPIO27{slash}ECAP4{slash}EQEP2S{slash}MFSXB-PadN11)") (class "Default")
      (node (ref "U3") (pin "N11") (pinfunction "GPIO27/ECAP4/EQEP2S/MFSXB_N11") (pintype "bidirectional"))
    )
    (net (code "190") (name "unconnected-(U3-GPIO28{slash}SCIRXDA{slash}~{XZCS6}-PadD10)") (class "Default")
      (node (ref "U3") (pin "D10") (pinfunction "GPIO28/SCIRXDA/~{XZCS6}_D10") (pintype "bidirectional"))
    )
    (net (code "191") (name "unconnected-(U3-GPIO35{slash}SCITXDA{slash}XR{slash}~{W}-PadB9)") (class "Default")
      (node (ref "U3") (pin "B9") (pinfunction "GPIO35/SCITXDA/XR/~{W}_B9") (pintype "bidirectional"))
    )
    (net (code "192") (name "unconnected-(U3-GPIO36{slash}SCIRXDA{slash}~{XZCS0}-PadC9)") (class "Default")
      (node (ref "U3") (pin "C9") (pinfunction "GPIO36/SCIRXDA/~{XZCS0}_C9") (pintype "bidirectional"))
    )
    (net (code "193") (name "unconnected-(U3-GPIO37{slash}ECAP2{slash}~{XZCS7}-PadB8)") (class "Default")
      (node (ref "U3") (pin "B8") (pinfunction "GPIO37/ECAP2/~{XZCS7}_B8") (pintype "bidirectional"))
    )
    (net (code "194") (name "unconnected-(U3-GPIO38{slash}~{XWE0}-PadC10)") (class "Default")
      (node (ref "U3") (pin "C10") (pinfunction "GPIO38/~{XWE0}_C10") (pintype "bidirectional"))
    )
    (net (code "195") (name "unconnected-(U3-GPIO39{slash}XA16-PadC3)") (class "Default")
      (node (ref "U3") (pin "C3") (pinfunction "GPIO39/XA16_C3") (pintype "bidirectional"))
    )
    (net (code "196") (name "unconnected-(U3-GPIO40{slash}XA0{slash}~{XWE1}-PadC8)") (class "Default")
      (node (ref "U3") (pin "C8") (pinfunction "GPIO40/XA0/~{XWE1}_C8") (pintype "bidirectional"))
    )
    (net (code "197") (name "unconnected-(U3-GPIO42{slash}XA2-PadB7)") (class "Default")
      (node (ref "U3") (pin "B7") (pinfunction "GPIO42/XA2_B7") (pintype "bidirectional"))
    )
    (net (code "198") (name "unconnected-(U3-GPIO43{slash}XA3-PadC7)") (class "Default")
      (node (ref "U3") (pin "C7") (pinfunction "GPIO43/XA3_C7") (pintype "bidirectional"))
    )
    (net (code "199") (name "unconnected-(U3-GPIO45{slash}XA5-PadB6)") (class "Default")
      (node (ref "U3") (pin "B6") (pinfunction "GPIO45/XA5_B6") (pintype "bidirectional"))
    )
    (net (code "200") (name "unconnected-(U3-GPIO46{slash}XA6-PadC6)") (class "Default")
      (node (ref "U3") (pin "C6") (pinfunction "GPIO46/XA6_C6") (pintype "bidirectional"))
    )
    (net (code "201") (name "unconnected-(U3-GPIO47{slash}XA7-PadD6)") (class "Default")
      (node (ref "U3") (pin "D6") (pinfunction "GPIO47/XA7_D6") (pintype "bidirectional"))
    )
    (net (code "202") (name "unconnected-(U3-GPIO48{slash}XD31{slash}ECAP5-PadL14)") (class "Default")
      (node (ref "U3") (pin "L14") (pinfunction "GPIO48/XD31/ECAP5_L14") (pintype "bidirectional"))
    )
    (net (code "203") (name "unconnected-(U3-GPIO49{slash}XD30{slash}ECAP6-PadL13)") (class "Default")
      (node (ref "U3") (pin "L13") (pinfunction "GPIO49/XD30/ECAP6_L13") (pintype "bidirectional"))
    )
    (net (code "204") (name "unconnected-(U3-GPIO50{slash}XD29{slash}EQEP1A-PadL12)") (class "Default")
      (node (ref "U3") (pin "L12") (pinfunction "GPIO50/XD29/EQEP1A_L12") (pintype "bidirectional"))
    )
    (net (code "205") (name "unconnected-(U3-GPIO51{slash}XD28{slash}EQEP1B-PadK14)") (class "Default")
      (node (ref "U3") (pin "K14") (pinfunction "GPIO51/XD28/EQEP1B_K14") (pintype "bidirectional"))
    )
    (net (code "206") (name "unconnected-(U3-GPIO52{slash}XD27{slash}EQEP1S-PadK13)") (class "Default")
      (node (ref "U3") (pin "K13") (pinfunction "GPIO52/XD27/EQEP1S_K13") (pintype "bidirectional"))
    )
    (net (code "207") (name "unconnected-(U3-GPIO53{slash}XD26{slash}EQEP1I-PadK12)") (class "Default")
      (node (ref "U3") (pin "K12") (pinfunction "GPIO53/XD26/EQEP1I_K12") (pintype "bidirectional"))
    )
    (net (code "208") (name "unconnected-(U3-GPIO57{slash}XD22{slash}~{SPISTEA}-PadH13)") (class "Default")
      (node (ref "U3") (pin "H13") (pinfunction "GPIO57/XD22/~{SPISTEA}_H13") (pintype "bidirectional"))
    )
    (net (code "209") (name "unconnected-(U3-GPIO58{slash}MCLKRA{slash}XD21-PadH12)") (class "Default")
      (node (ref "U3") (pin "H12") (pinfunction "GPIO58/MCLKRA/XD21_H12") (pintype "bidirectional"))
    )
    (net (code "210") (name "unconnected-(U3-GPIO59{slash}MFSRA{slash}XD20-PadH11)") (class "Default")
      (node (ref "U3") (pin "H11") (pinfunction "GPIO59/MFSRA/XD20_H11") (pintype "bidirectional"))
    )
    (net (code "211") (name "unconnected-(U3-GPIO60{slash}MCLKRB{slash}XD19-PadG12)") (class "Default")
      (node (ref "U3") (pin "G12") (pinfunction "GPIO60/MCLKRB/XD19_G12") (pintype "bidirectional"))
    )
    (net (code "212") (name "unconnected-(U3-GPIO61{slash}MFSRB{slash}XD18-PadF14)") (class "Default")
      (node (ref "U3") (pin "F14") (pinfunction "GPIO61/MFSRB/XD18_F14") (pintype "bidirectional"))
    )
    (net (code "213") (name "unconnected-(U3-GPIO62{slash}SCIRXDC{slash}XD17-PadF13)") (class "Default")
      (node (ref "U3") (pin "F13") (pinfunction "GPIO62/SCIRXDC/XD17_F13") (pintype "bidirectional"))
    )
    (net (code "214") (name "unconnected-(U3-GPIO63{slash}SCITXDC{slash}XD16-PadF12)") (class "Default")
      (node (ref "U3") (pin "F12") (pinfunction "GPIO63/SCITXDC/XD16_F12") (pintype "bidirectional"))
    )
    (net (code "215") (name "unconnected-(U3-GPIO64{slash}XD15-PadE14)") (class "Default")
      (node (ref "U3") (pin "E14") (pinfunction "GPIO64/XD15_E14") (pintype "bidirectional"))
    )
    (net (code "216") (name "unconnected-(U3-GPIO65{slash}XD14-PadE13)") (class "Default")
      (node (ref "U3") (pin "E13") (pinfunction "GPIO65/XD14_E13") (pintype "bidirectional"))
    )
    (net (code "217") (name "unconnected-(U3-GPIO66{slash}XD13-PadE12)") (class "Default")
      (node (ref "U3") (pin "E12") (pinfunction "GPIO66/XD13_E12") (pintype "bidirectional"))
    )
    (net (code "218") (name "unconnected-(U3-GPIO68{slash}XD11-PadD13)") (class "Default")
      (node (ref "U3") (pin "D13") (pinfunction "GPIO68/XD11_D13") (pintype "bidirectional"))
    )
    (net (code "219") (name "unconnected-(U3-GPIO69{slash}XD10-PadD12)") (class "Default")
      (node (ref "U3") (pin "D12") (pinfunction "GPIO69/XD10_D12") (pintype "bidirectional"))
    )
    (net (code "220") (name "unconnected-(U3-GPIO71{slash}XD8-PadC13)") (class "Default")
      (node (ref "U3") (pin "C13") (pinfunction "GPIO71/XD8_C13") (pintype "bidirectional"))
    )
    (net (code "221") (name "unconnected-(U3-GPIO72{slash}XD7-PadB13)") (class "Default")
      (node (ref "U3") (pin "B13") (pinfunction "GPIO72/XD7_B13") (pintype "bidirectional"))
    )
    (net (code "222") (name "unconnected-(U3-GPIO73{slash}XD6-PadA12)") (class "Default")
      (node (ref "U3") (pin "A12") (pinfunction "GPIO73/XD6_A12") (pintype "bidirectional"))
    )
    (net (code "223") (name "unconnected-(U3-GPIO74{slash}XD5-PadB12)") (class "Default")
      (node (ref "U3") (pin "B12") (pinfunction "GPIO74/XD5_B12") (pintype "bidirectional"))
    )
    (net (code "224") (name "unconnected-(U3-GPIO75{slash}XD4-PadC12)") (class "Default")
      (node (ref "U3") (pin "C12") (pinfunction "GPIO75/XD4_C12") (pintype "bidirectional"))
    )
    (net (code "225") (name "unconnected-(U3-GPIO76{slash}XD3-PadA11)") (class "Default")
      (node (ref "U3") (pin "A11") (pinfunction "GPIO76/XD3_A11") (pintype "bidirectional"))
    )
    (net (code "226") (name "unconnected-(U3-GPIO77{slash}XD2-PadB11)") (class "Default")
      (node (ref "U3") (pin "B11") (pinfunction "GPIO77/XD2_B11") (pintype "bidirectional"))
    )
    (net (code "227") (name "unconnected-(U3-GPIO78{slash}XD1-PadC11)") (class "Default")
      (node (ref "U3") (pin "C11") (pinfunction "GPIO78/XD1_C11") (pintype "bidirectional"))
    )
    (net (code "228") (name "unconnected-(U3-GPIO79{slash}XD0-PadB10)") (class "Default")
      (node (ref "U3") (pin "B10") (pinfunction "GPIO79/XD0_B10") (pintype "bidirectional"))
    )
    (net (code "229") (name "unconnected-(U3-GPIO80{slash}XA8-PadA5)") (class "Default")
      (node (ref "U3") (pin "A5") (pinfunction "GPIO80/XA8_A5") (pintype "bidirectional"))
    )
    (net (code "230") (name "unconnected-(U3-GPIO81{slash}XA9-PadB5)") (class "Default")
      (node (ref "U3") (pin "B5") (pinfunction "GPIO81/XA9_B5") (pintype "bidirectional"))
    )
    (net (code "231") (name "unconnected-(U3-GPIO82{slash}XA10-PadC5)") (class "Default")
      (node (ref "U3") (pin "C5") (pinfunction "GPIO82/XA10_C5") (pintype "bidirectional"))
    )
    (net (code "232") (name "unconnected-(U3-GPIO83{slash}XA11-PadA4)") (class "Default")
      (node (ref "U3") (pin "A4") (pinfunction "GPIO83/XA11_A4") (pintype "bidirectional"))
    )
    (net (code "233") (name "unconnected-(U3-GPIO84{slash}XA12-PadB4)") (class "Default")
      (node (ref "U3") (pin "B4") (pinfunction "GPIO84/XA12_B4") (pintype "bidirectional"))
    )
    (net (code "234") (name "unconnected-(U3-GPIO85{slash}XA13-PadC4)") (class "Default")
      (node (ref "U3") (pin "C4") (pinfunction "GPIO85/XA13_C4") (pintype "bidirectional"))
    )
    (net (code "235") (name "unconnected-(U3-GPIO86{slash}XA14-PadA3)") (class "Default")
      (node (ref "U3") (pin "A3") (pinfunction "GPIO86/XA14_A3") (pintype "bidirectional"))
    )
    (net (code "236") (name "unconnected-(U3-GPIO87{slash}XA15-PadB3)") (class "Default")
      (node (ref "U3") (pin "B3") (pinfunction "GPIO87/XA15_B3") (pintype "bidirectional"))
    )
    (net (code "237") (name "unconnected-(U3-TEST1-PadM7)") (class "Default")
      (node (ref "U3") (pin "M7") (pinfunction "TEST1_M7") (pintype "bidirectional"))
    )
    (net (code "238") (name "unconnected-(U3-TEST2-PadL7)") (class "Default")
      (node (ref "U3") (pin "L7") (pinfunction "TEST2_L7") (pintype "bidirectional"))
    )
    (net (code "239") (name "unconnected-(U3-XCLKOUT-PadA10)") (class "Default")
      (node (ref "U3") (pin "A10") (pinfunction "XCLKOUT_A10") (pintype "bidirectional"))
    )
    (net (code "240") (name "unconnected-(U3-~{XRD}-PadA8)") (class "Default")
      (node (ref "U3") (pin "A8") (pinfunction "~{XRD}_A8") (pintype "bidirectional"))
    )
    (net (code "241") (name "unconnected-(U7-NC-Pad1D)") (class "Default")
      (node (ref "U7") (pin "1D") (pinfunction "NC_1D") (pintype "bidirectional"))
    )
    (net (code "242") (name "unconnected-(U7-NC-Pad2D)") (class "Default")
      (node (ref "U7") (pin "2D") (pinfunction "NC_2D") (pintype "bidirectional"))
    )
    (net (code "243") (name "unconnected-(U18-VREF-Pad5)") (class "Default")
      (node (ref "U18") (pin "5") (pinfunction "VREF_5") (pintype "output"))
    )
    (net (code "244") (name "~{LED0}") (class "Default")
      (node (ref "U3") (pin "C14") (pinfunction "GPIO70/XD9_C14") (pintype "bidirectional"))
      (node (ref "U6") (pin "1") (pinfunction "1A_1") (pintype "bidirectional"))
    )
    (net (code "245") (name "~{LED1}") (class "Default")
      (node (ref "U3") (pin "D14") (pinfunction "GPIO67/XD12_D14") (pintype "bidirectional"))
      (node (ref "U6") (pin "3") (pinfunction "2A_3") (pintype "bidirectional"))
    )
    (net (code "246") (name "~{TRST}") (class "Default")
      (node (ref "C29") (pin "1") (pinfunction "1_1") (pintype "passive"))
      (node (ref "R3") (pin "1") (pinfunction "1_1") (pintype "passive"))
      (node (ref "S1") (pin "2") (pinfunction "1_2") (pintype "bidirectional"))
      (node (ref "U3") (pin "L11") (pinfunction "~{TRST}_L11") (pintype "bidirectional"))
    )
  )
)
